# design.net
KiCad netlist of a schematic drawn in EasyEDA Pro
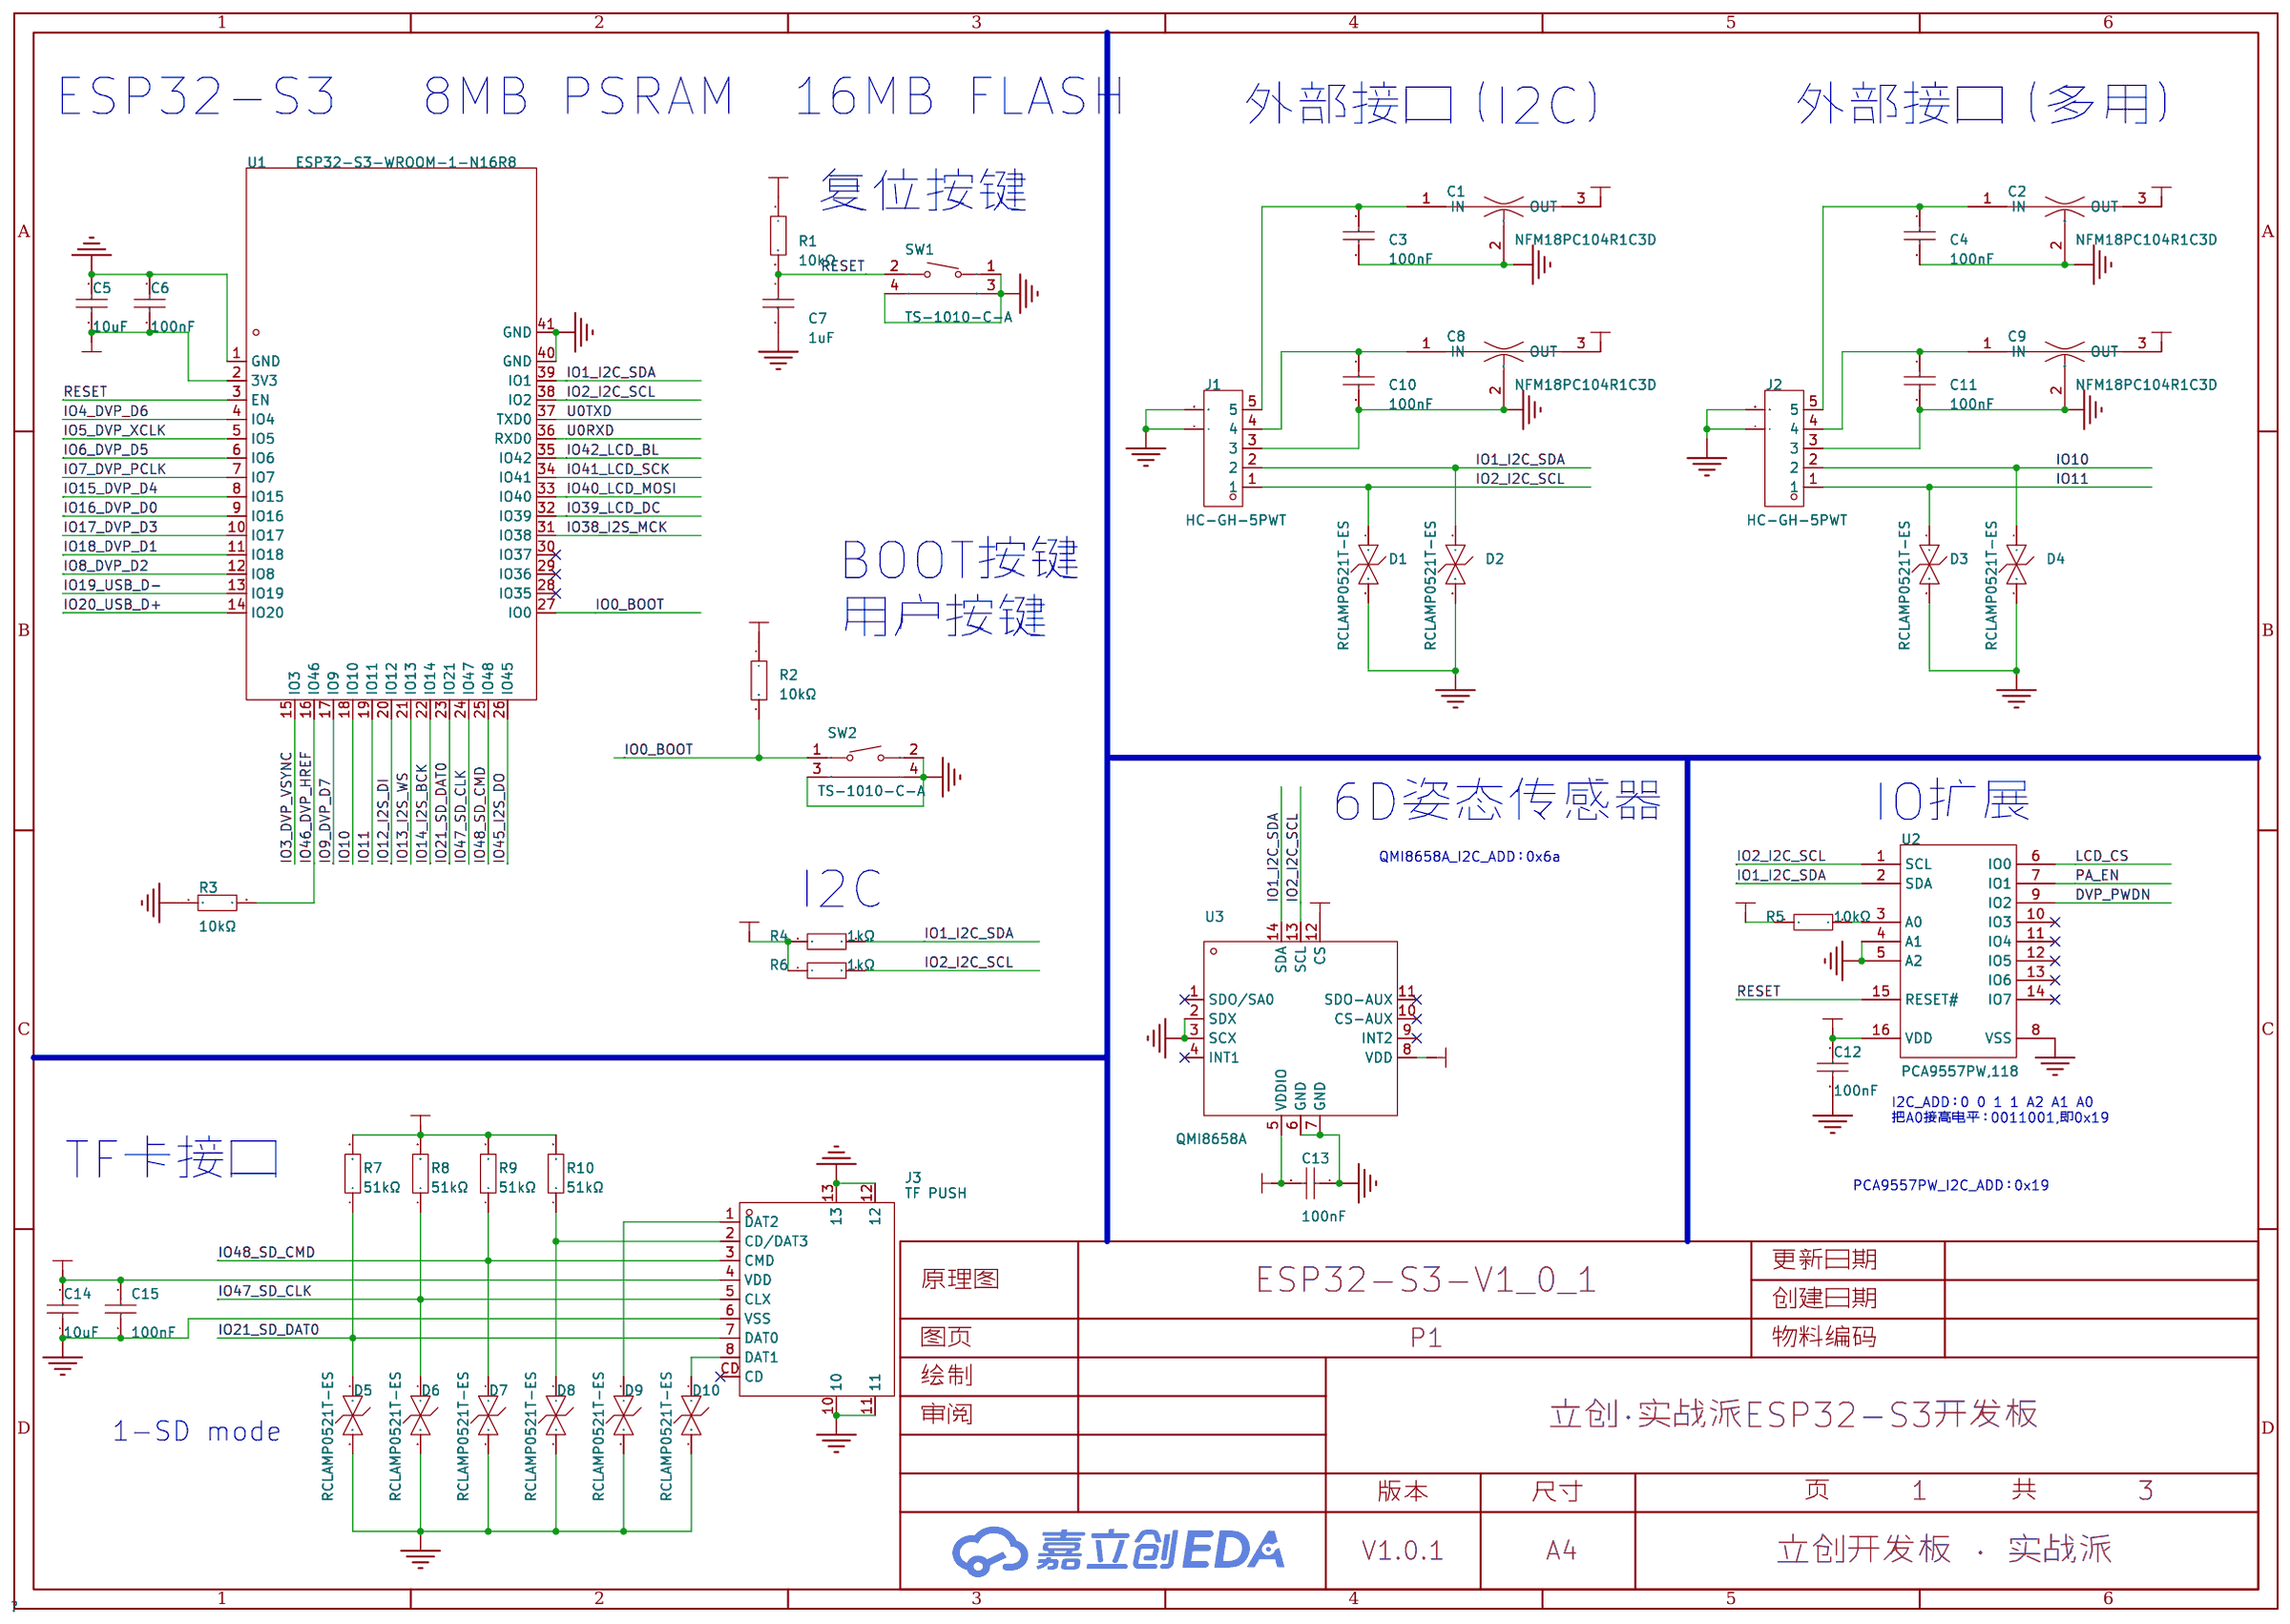
[diagram p0: P1]
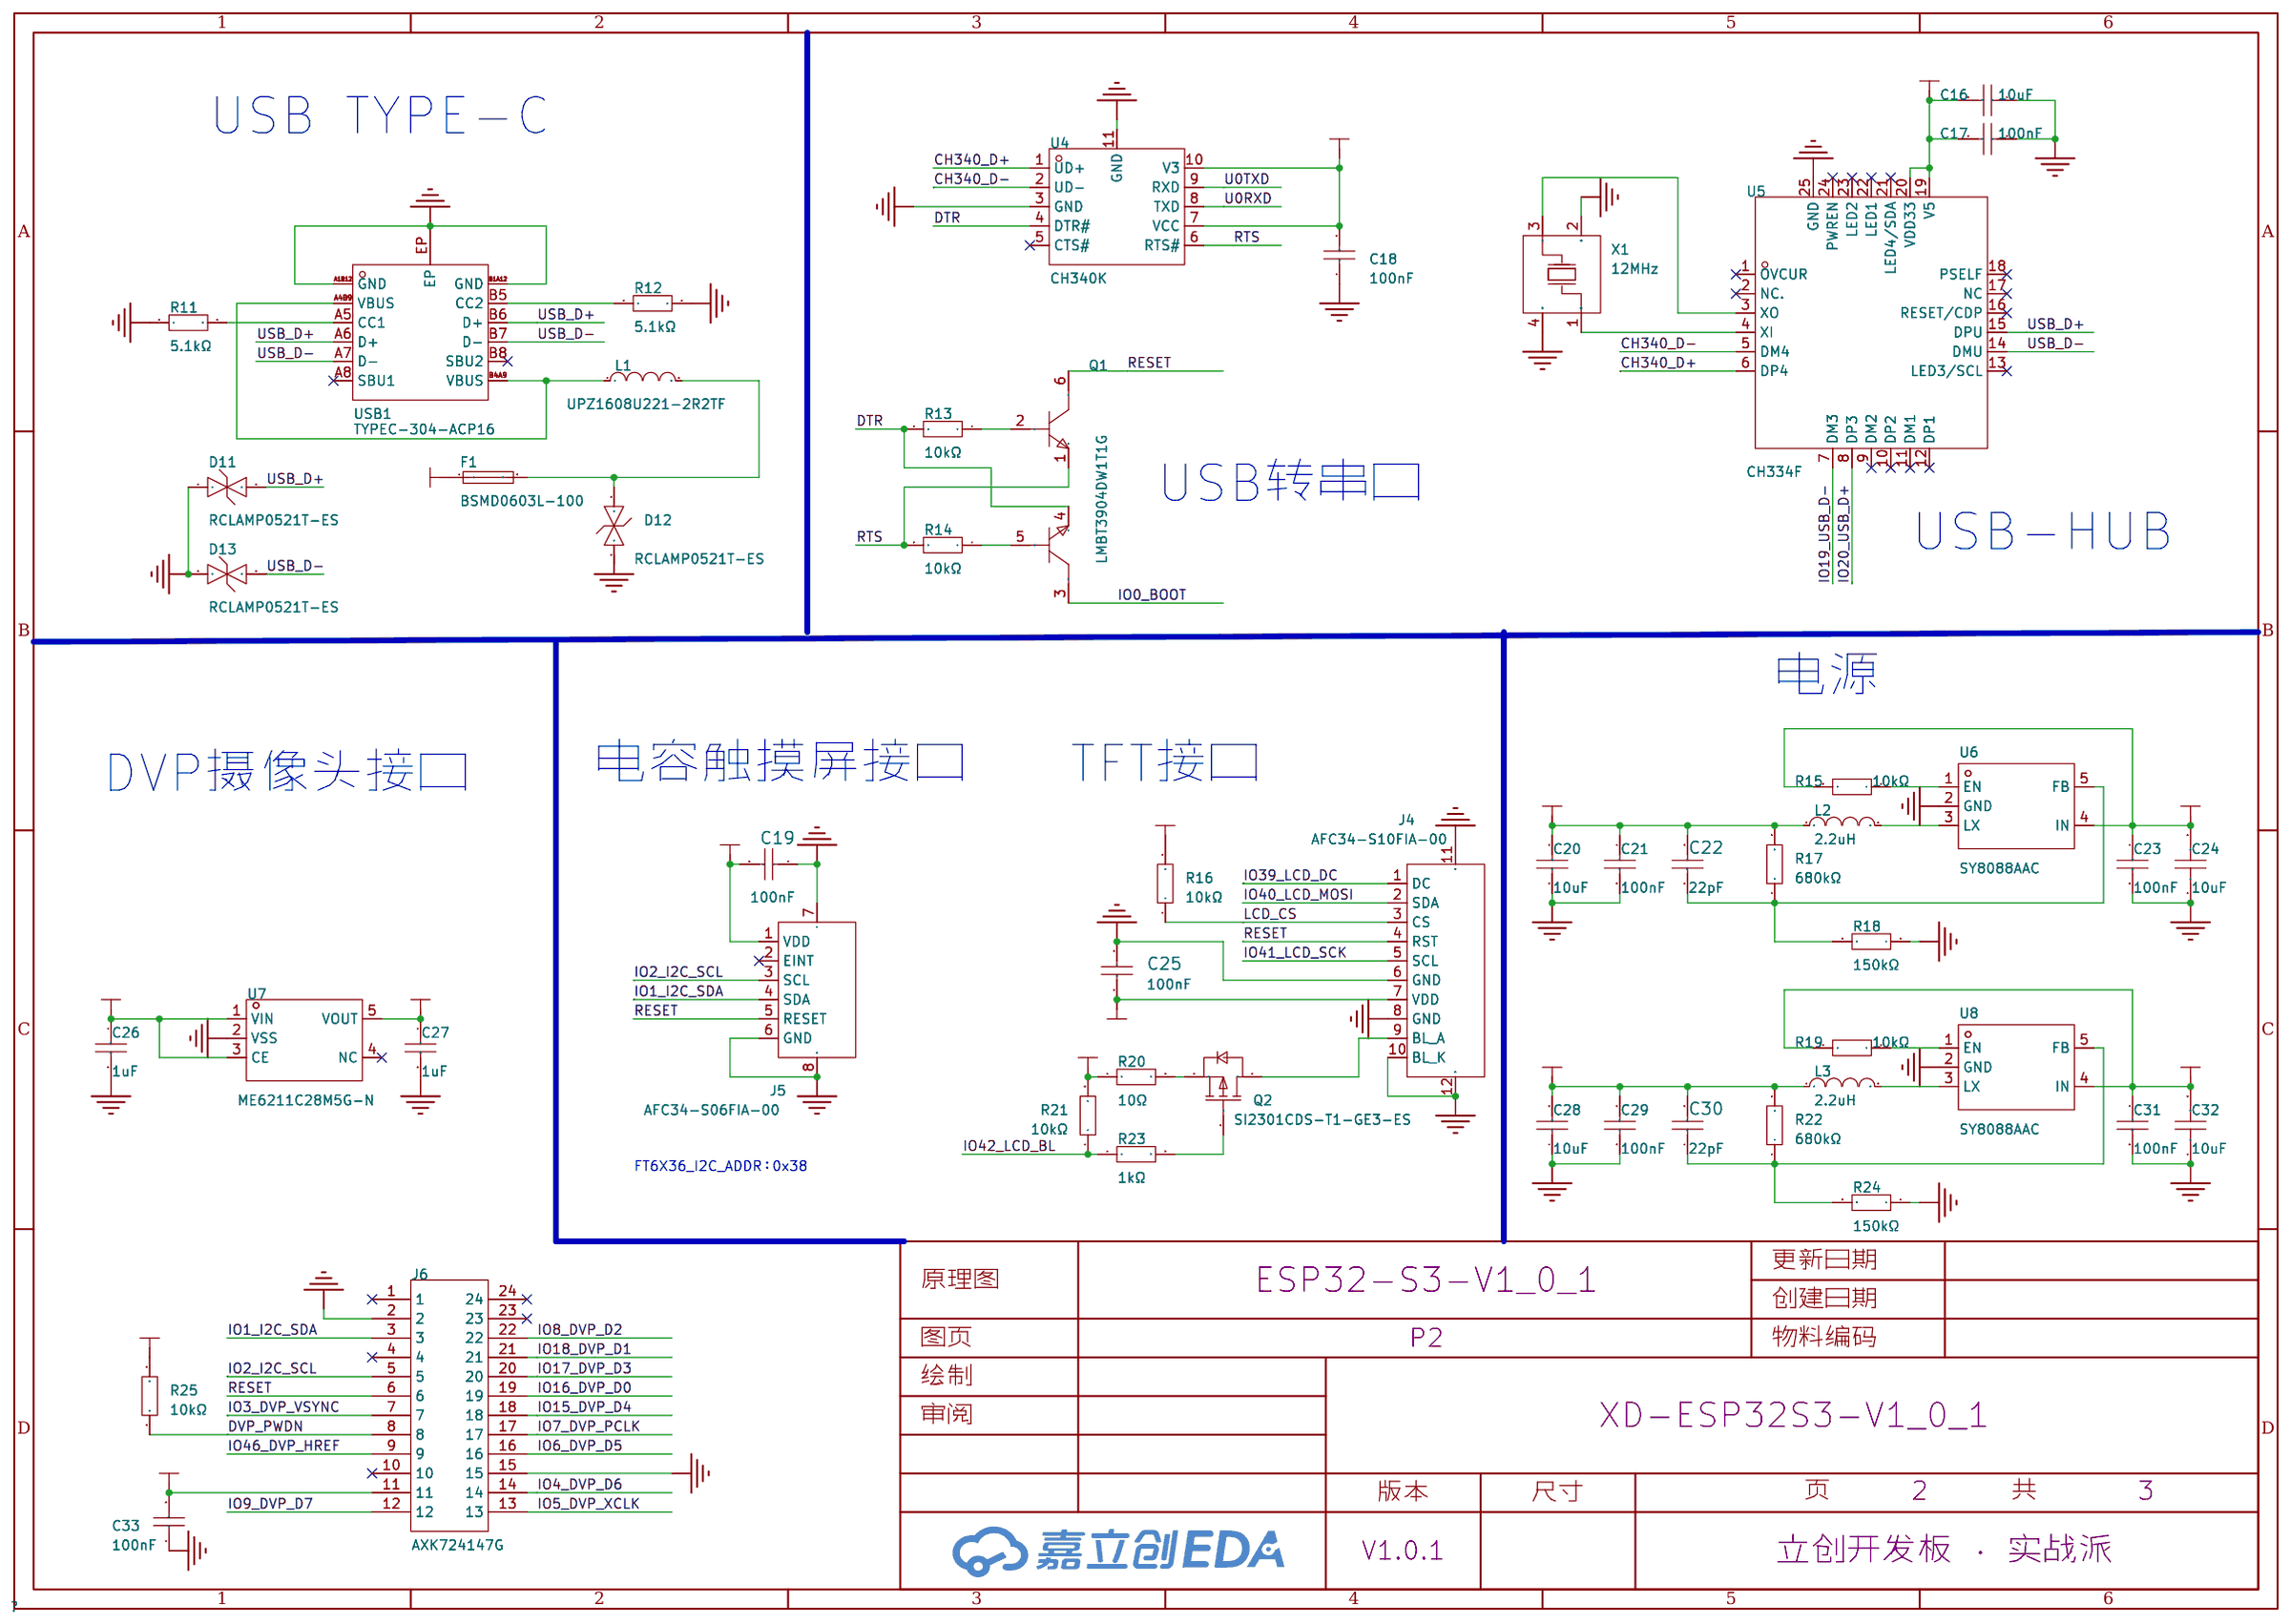
[diagram p1: P2]
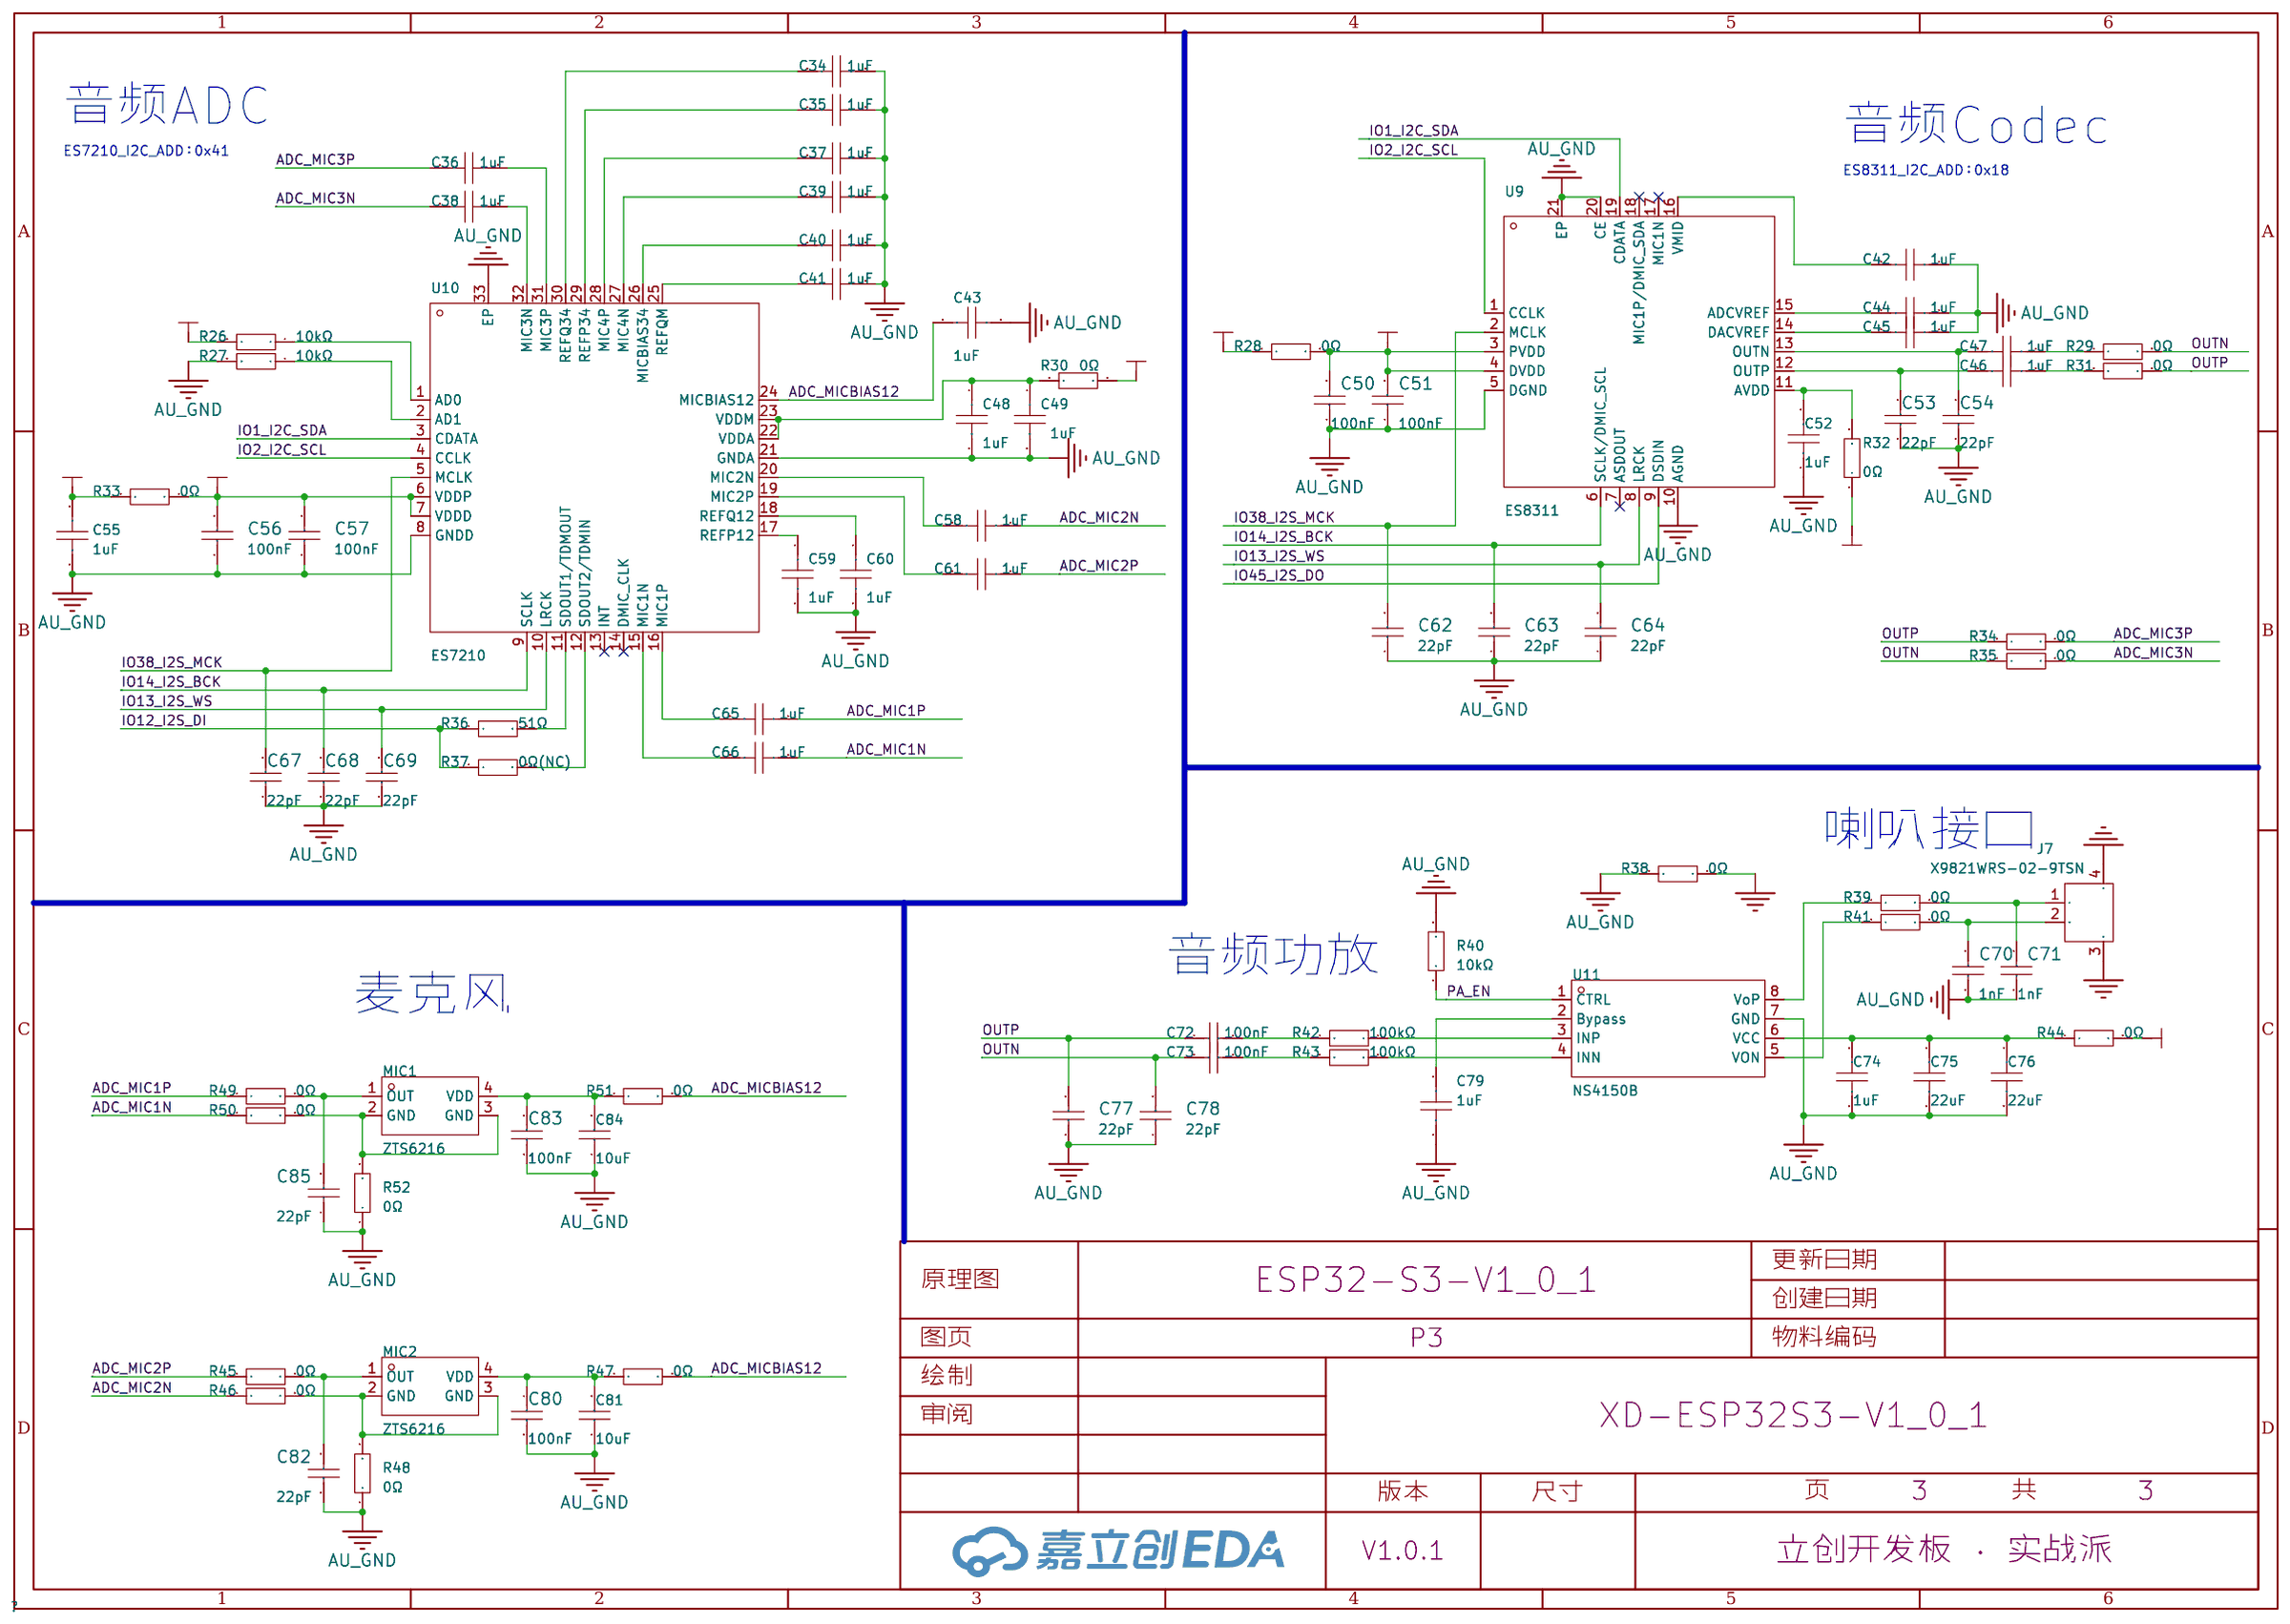
[diagram p2: P3]

(export (version "E")
  (design (tool "Eeschema 10.0.6"))
  (components
    (comp (ref "C1")
      (value "NFM18PC104R1C3D")
      (footprint "easyedapro:FILTER-SMD_3P-L1.6-W0.8-L_NFM18CC223R1C3D")
      (description "电容量:100nF;精度:±20%;直流电阻:30mΩ;")
      (fields (field (name "Manufacturer") "muRata(村田)"))
      (libsource (lib "easyedapro") (part "NFM15PC104D0J3D"))
    )
    (comp (ref "C2")
      (value "NFM18PC104R1C3D")
      (footprint "easyedapro:FILTER-SMD_3P-L1.6-W0.8-L_NFM18CC223R1C3D")
      (description "电容量:100nF;精度:±20%;直流电阻:30mΩ;")
      (fields (field (name "Manufacturer") "muRata(村田)"))
      (libsource (lib "easyedapro") (part "NFM15PC104D0J3D"))
    )
    (comp (ref "C3")
      (value "100nF")
      (footprint "easyedapro:C0402")
      (description "容值:100nF;精度:±10%;额定电压:16V;材质(温度系数):X7R;")
      (fields
        (field (name "Manufacturer Part") "CL05B104KO5NNNC")
        (field (name "Manufacturer") "SAMSUNG(三星)")
      )
      (libsource (lib "easyedapro") (part "CL05B104KO5NNNC"))
    )
    (comp (ref "C4")
      (value "100nF")
      (footprint "easyedapro:C0402")
      (description "容值:100nF;精度:±10%;额定电压:16V;材质(温度系数):X7R;")
      (fields
        (field (name "Manufacturer Part") "CL05B104KO5NNNC")
        (field (name "Manufacturer") "SAMSUNG(三星)")
      )
      (libsource (lib "easyedapro") (part "CL05B104KO5NNNC"))
    )
    (comp (ref "C5")
      (value "10uF")
      (footprint "easyedapro:C0402")
      (description "容值:10uF;精度:±20%;额定电压:6.3V;材质(温度系数):X5R;")
      (fields
        (field (name "Manufacturer Part") "CL05A106MQ5NUNC")
        (field (name "Manufacturer") "SAMSUNG(三星)")
      )
      (libsource (lib "easyedapro") (part "CL05A106MQ5NUNC"))
    )
    (comp (ref "C6")
      (value "100nF")
      (footprint "easyedapro:C0402")
      (description "容值:100nF;精度:±10%;额定电压:16V;材质(温度系数):X7R;")
      (fields
        (field (name "Manufacturer Part") "CL05B104KO5NNNC")
        (field (name "Manufacturer") "SAMSUNG(三星)")
      )
      (libsource (lib "easyedapro") (part "CL05B104KO5NNNC"))
    )
    (comp (ref "C7")
      (value "1uF")
      (footprint "easyedapro:C0402")
      (description "容值:100nF;精度:±10%;额定电压:16V;材质(温度系数):X7R;")
      (fields
        (field (name "Manufacturer Part") "CL05A105KA5NQNC")
        (field (name "Manufacturer") "SAMSUNG(三星)")
      )
      (libsource (lib "easyedapro") (part "CL05B104KO5NNNC"))
    )
    (comp (ref "C8")
      (value "NFM18PC104R1C3D")
      (footprint "easyedapro:FILTER-SMD_3P-L1.6-W0.8-L_NFM18CC223R1C3D")
      (description "电容量:100nF;精度:±20%;直流电阻:30mΩ;")
      (fields (field (name "Manufacturer") "muRata(村田)"))
      (libsource (lib "easyedapro") (part "NFM15PC104D0J3D"))
    )
    (comp (ref "C9")
      (value "NFM18PC104R1C3D")
      (footprint "easyedapro:FILTER-SMD_3P-L1.6-W0.8-L_NFM18CC223R1C3D")
      (description "电容量:100nF;精度:±20%;直流电阻:30mΩ;")
      (fields (field (name "Manufacturer") "muRata(村田)"))
      (libsource (lib "easyedapro") (part "NFM15PC104D0J3D"))
    )
    (comp (ref "C10")
      (value "100nF")
      (footprint "easyedapro:C0402")
      (description "容值:100nF;精度:±10%;额定电压:16V;材质(温度系数):X7R;")
      (fields
        (field (name "Manufacturer Part") "CL05B104KO5NNNC")
        (field (name "Manufacturer") "SAMSUNG(三星)")
      )
      (libsource (lib "easyedapro") (part "CL05B104KO5NNNC"))
    )
    (comp (ref "C11")
      (value "100nF")
      (footprint "easyedapro:C0402")
      (description "容值:100nF;精度:±10%;额定电压:16V;材质(温度系数):X7R;")
      (fields
        (field (name "Manufacturer Part") "CL05B104KO5NNNC")
        (field (name "Manufacturer") "SAMSUNG(三星)")
      )
      (libsource (lib "easyedapro") (part "CL05B104KO5NNNC"))
    )
    (comp (ref "C12")
      (value "100nF")
      (footprint "easyedapro:C0402")
      (description "容值:100nF;精度:±10%;额定电压:16V;材质(温度系数):X7R;")
      (fields
        (field (name "Manufacturer Part") "CL05B104KO5NNNC")
        (field (name "Manufacturer") "SAMSUNG(三星)")
      )
      (libsource (lib "easyedapro") (part "CL05B104KO5NNNC"))
    )
    (comp (ref "C13")
      (value "100nF")
      (footprint "easyedapro:C0402")
      (description "容值:100nF;精度:±10%;额定电压:16V;材质(温度系数):X7R;")
      (fields
        (field (name "Manufacturer Part") "CL05B104KO5NNNC")
        (field (name "Manufacturer") "SAMSUNG(三星)")
      )
      (libsource (lib "easyedapro") (part "CL05B104KO5NNNC"))
    )
    (comp (ref "C14")
      (value "10uF")
      (footprint "easyedapro:C0402")
      (description "容值:10uF;精度:±20%;额定电压:6.3V;材质(温度系数):X5R;")
      (fields
        (field (name "Manufacturer Part") "CL05A106MQ5NUNC")
        (field (name "Manufacturer") "SAMSUNG(三星)")
      )
      (libsource (lib "easyedapro") (part "CL05A106MQ5NUNC"))
    )
    (comp (ref "C15")
      (value "100nF")
      (footprint "easyedapro:C0402")
      (description "容值:100nF;精度:±10%;额定电压:16V;材质(温度系数):X7R;")
      (fields
        (field (name "Manufacturer Part") "CL05B104KO5NNNC")
        (field (name "Manufacturer") "SAMSUNG(三星)")
      )
      (libsource (lib "easyedapro") (part "CL05B104KO5NNNC"))
    )
    (comp (ref "D1")
      (value "RCLAMP0521T-ES")
      (footprint "easyedapro:DFN1006-2L-BI")
      (description "反向关断电压（典型值）:5V(Max) 击穿电压（最小值）:6.0V 箝位电压:12V 峰值脉冲电流:4A (8/20us) 极性:Bidirectional")
      (fields (field (name "Manufacturer") "ElecSuper(静芯微）"))
      (libsource (lib "easyedapro") (part "RCLAMP0521T-ES"))
    )
    (comp (ref "D2")
      (value "RCLAMP0521T-ES")
      (footprint "easyedapro:DFN1006-2L-BI")
      (description "反向关断电压（典型值）:5V(Max) 击穿电压（最小值）:6.0V 箝位电压:12V 峰值脉冲电流:4A (8/20us) 极性:Bidirectional")
      (fields (field (name "Manufacturer") "ElecSuper(静芯微）"))
      (libsource (lib "easyedapro") (part "RCLAMP0521T-ES"))
    )
    (comp (ref "D3")
      (value "RCLAMP0521T-ES")
      (footprint "easyedapro:DFN1006-2L-BI")
      (description "反向关断电压（典型值）:5V(Max) 击穿电压（最小值）:6.0V 箝位电压:12V 峰值脉冲电流:4A (8/20us) 极性:Bidirectional")
      (fields (field (name "Manufacturer") "ElecSuper(静芯微）"))
      (libsource (lib "easyedapro") (part "RCLAMP0521T-ES"))
    )
    (comp (ref "D4")
      (value "RCLAMP0521T-ES")
      (footprint "easyedapro:DFN1006-2L-BI")
      (description "反向关断电压（典型值）:5V(Max) 击穿电压（最小值）:6.0V 箝位电压:12V 峰值脉冲电流:4A (8/20us) 极性:Bidirectional")
      (fields (field (name "Manufacturer") "ElecSuper(静芯微）"))
      (libsource (lib "easyedapro") (part "RCLAMP0521T-ES"))
    )
    (comp (ref "D5")
      (value "RCLAMP0521T-ES")
      (footprint "easyedapro:DFN1006-2L-BI")
      (description "反向关断电压（典型值）:5V(Max) 击穿电压（最小值）:6.0V 箝位电压:12V 峰值脉冲电流:4A (8/20us) 极性:Bidirectional")
      (fields (field (name "Manufacturer") "ElecSuper(静芯微）"))
      (libsource (lib "easyedapro") (part "RCLAMP0521T-ES"))
    )
    (comp (ref "D6")
      (value "RCLAMP0521T-ES")
      (footprint "easyedapro:DFN1006-2L-BI")
      (description "反向关断电压（典型值）:5V(Max) 击穿电压（最小值）:6.0V 箝位电压:12V 峰值脉冲电流:4A (8/20us) 极性:Bidirectional")
      (fields (field (name "Manufacturer") "ElecSuper(静芯微）"))
      (libsource (lib "easyedapro") (part "RCLAMP0521T-ES"))
    )
    (comp (ref "D7")
      (value "RCLAMP0521T-ES")
      (footprint "easyedapro:DFN1006-2L-BI")
      (description "反向关断电压（典型值）:5V(Max) 击穿电压（最小值）:6.0V 箝位电压:12V 峰值脉冲电流:4A (8/20us) 极性:Bidirectional")
      (fields (field (name "Manufacturer") "ElecSuper(静芯微）"))
      (libsource (lib "easyedapro") (part "RCLAMP0521T-ES"))
    )
    (comp (ref "D8")
      (value "RCLAMP0521T-ES")
      (footprint "easyedapro:DFN1006-2L-BI")
      (description "反向关断电压（典型值）:5V(Max) 击穿电压（最小值）:6.0V 箝位电压:12V 峰值脉冲电流:4A (8/20us) 极性:Bidirectional")
      (fields (field (name "Manufacturer") "ElecSuper(静芯微）"))
      (libsource (lib "easyedapro") (part "RCLAMP0521T-ES"))
    )
    (comp (ref "D9")
      (value "RCLAMP0521T-ES")
      (footprint "easyedapro:DFN1006-2L-BI")
      (description "反向关断电压（典型值）:5V(Max) 击穿电压（最小值）:6.0V 箝位电压:12V 峰值脉冲电流:4A (8/20us) 极性:Bidirectional")
      (fields (field (name "Manufacturer") "ElecSuper(静芯微）"))
      (libsource (lib "easyedapro") (part "RCLAMP0521T-ES"))
    )
    (comp (ref "D10")
      (value "RCLAMP0521T-ES")
      (footprint "easyedapro:DFN1006-2L-BI")
      (description "反向关断电压（典型值）:5V(Max) 击穿电压（最小值）:6.0V 箝位电压:12V 峰值脉冲电流:4A (8/20us) 极性:Bidirectional")
      (fields (field (name "Manufacturer") "ElecSuper(静芯微）"))
      (libsource (lib "easyedapro") (part "RCLAMP0521T-ES"))
    )
    (comp (ref "J1")
      (value "HC-GH-5PWT")
      (footprint "easyedapro:CONN-SMD_5P-P1.25_HC-GH-5PWTKK")
      (description "插针结构:1x5P;间距:1.25mm;公母:公;安装方式:卧贴;排数:1;每排PIN数:5;参考系列:GH;额定电流:1A;工作温度范围:-25°C~+85°C;")
      (fields (field (name "Manufacturer") "HCTL(华灿天禄)"))
      (libsource (lib "easyedapro") (part "HC-GH-5PWT_C3011947"))
    )
    (comp (ref "J2")
      (value "HC-GH-5PWT")
      (footprint "easyedapro:CONN-SMD_5P-P1.25_HC-GH-5PWTKK")
      (description "插针结构:1x5P;间距:1.25mm;公母:公;安装方式:卧贴;排数:1;每排PIN数:5;参考系列:GH;额定电流:1A;工作温度范围:-25°C~+85°C;")
      (fields (field (name "Manufacturer") "HCTL(华灿天禄)"))
      (libsource (lib "easyedapro") (part "HC-GH-5PWT_C3011947"))
    )
    (comp (ref "J3")
      (value "TF PUSH")
      (footprint "easyedapro:TF-SMD_TF-PUSH")
      (description "卡连接方式:自弹式;卡类型:MicroSD卡(TF卡);连接器类型:卡座;本体最大高度:2mm;触头材质:-;触头镀层:-;工作温度范围:-20°C~+90°C;焊接温度(最大值):-;")
      (fields (field (name "Manufacturer") "SHOU HAN(首韩)"))
      (libsource (lib "easyedapro") (part "TF PUSH"))
    )
    (comp (ref "R1")
      (value "10kΩ")
      (footprint "easyedapro:R0402")
      (description "电阻类型:厚膜电阻;阻值:10kΩ;精度:±1%;功率:62.5mW;温度系数:±100ppm/°C;")
      (fields
        (field (name "Manufacturer Part") "0402WGF1002TCE")
        (field (name "Manufacturer") "UNI-ROYAL(厚声)")
      )
      (libsource (lib "easyedapro") (part "0402WGF1002TCE"))
    )
    (comp (ref "R2")
      (value "10kΩ")
      (footprint "easyedapro:R0402")
      (description "电阻类型:厚膜电阻;阻值:10kΩ;精度:±1%;功率:62.5mW;温度系数:±100ppm/°C;")
      (fields
        (field (name "Manufacturer Part") "0402WGF1002TCE")
        (field (name "Manufacturer") "UNI-ROYAL(厚声)")
      )
      (libsource (lib "easyedapro") (part "0402WGF1002TCE"))
    )
    (comp (ref "R3")
      (value "10kΩ")
      (footprint "easyedapro:R0402")
      (description "电阻类型:厚膜电阻;阻值:10kΩ;精度:±1%;功率:62.5mW;温度系数:±100ppm/°C;")
      (fields
        (field (name "Manufacturer Part") "0402WGF1002TCE")
        (field (name "Manufacturer") "UNI-ROYAL(厚声)")
      )
      (libsource (lib "easyedapro") (part "0402WGF1002TCE"))
    )
    (comp (ref "R4")
      (value "1kΩ")
      (footprint "easyedapro:R0402")
      (description "电阻类型:厚膜电阻;阻值:1kΩ;精度:±1%;功率:62.5mW;")
      (fields
        (field (name "Manufacturer Part") "0402WGF1001TCE")
        (field (name "Manufacturer") "UNI-ROYAL(厚声)")
      )
      (libsource (lib "easyedapro") (part "0402WGF1001TCE"))
    )
    (comp (ref "R5")
      (value "10kΩ")
      (footprint "easyedapro:R0402")
      (description "电阻类型:厚膜电阻;阻值:10kΩ;精度:±1%;功率:62.5mW;温度系数:±100ppm/°C;")
      (fields
        (field (name "Manufacturer Part") "0402WGF1002TCE")
        (field (name "Manufacturer") "UNI-ROYAL(厚声)")
      )
      (libsource (lib "easyedapro") (part "0402WGF1002TCE"))
    )
    (comp (ref "R6")
      (value "1kΩ")
      (footprint "easyedapro:R0402")
      (description "电阻类型:厚膜电阻;阻值:1kΩ;精度:±1%;功率:62.5mW;")
      (fields
        (field (name "Manufacturer Part") "0402WGF1001TCE")
        (field (name "Manufacturer") "UNI-ROYAL(厚声)")
      )
      (libsource (lib "easyedapro") (part "0402WGF1001TCE"))
    )
    (comp (ref "R7")
      (value "51kΩ")
      (footprint "easyedapro:R0402")
      (description "电阻类型:厚膜电阻;阻值:51kΩ;精度:±1%;功率:62.5mW;最大工作电压:50V;温度系数:±100ppm/°C;")
      (fields
        (field (name "Manufacturer Part") "0402WGF5102TCE")
        (field (name "Manufacturer") "UNI-ROYAL(厚声)")
      )
      (libsource (lib "easyedapro") (part "0402WGF5102TCE"))
    )
    (comp (ref "R8")
      (value "51kΩ")
      (footprint "easyedapro:R0402")
      (description "电阻类型:厚膜电阻;阻值:51kΩ;精度:±1%;功率:62.5mW;最大工作电压:50V;温度系数:±100ppm/°C;")
      (fields
        (field (name "Manufacturer Part") "0402WGF5102TCE")
        (field (name "Manufacturer") "UNI-ROYAL(厚声)")
      )
      (libsource (lib "easyedapro") (part "0402WGF5102TCE"))
    )
    (comp (ref "R9")
      (value "51kΩ")
      (footprint "easyedapro:R0402")
      (description "电阻类型:厚膜电阻;阻值:51kΩ;精度:±1%;功率:62.5mW;最大工作电压:50V;温度系数:±100ppm/°C;")
      (fields
        (field (name "Manufacturer Part") "0402WGF5102TCE")
        (field (name "Manufacturer") "UNI-ROYAL(厚声)")
      )
      (libsource (lib "easyedapro") (part "0402WGF5102TCE"))
    )
    (comp (ref "R10")
      (value "51kΩ")
      (footprint "easyedapro:R0402")
      (description "电阻类型:厚膜电阻;阻值:51kΩ;精度:±1%;功率:62.5mW;最大工作电压:50V;温度系数:±100ppm/°C;")
      (fields
        (field (name "Manufacturer Part") "0402WGF5102TCE")
        (field (name "Manufacturer") "UNI-ROYAL(厚声)")
      )
      (libsource (lib "easyedapro") (part "0402WGF5102TCE"))
    )
    (comp (ref "SW1")
      (value "TS-1010-C-A")
      (footprint "easyedapro:KEY-SMD_TX-1010-X-X")
      (fields (field (name "Manufacturer") "XKB Connectivity(中国星坤)"))
      (libsource (lib "easyedapro") (part "TS-1010-C-A"))
    )
    (comp (ref "SW2")
      (value "TS-1010-C-A")
      (footprint "easyedapro:KEY-SMD_TX-1010-X-X")
      (fields (field (name "Manufacturer") "XKB Connectivity(中国星坤)"))
      (libsource (lib "easyedapro") (part "TS-1010-C-A"))
    )
    (comp (ref "U1")
      (value "ESP32-S3-WROOM-1-N16R8")
      (footprint "easyedapro:WIRELM-SMD_ESP32-S3-WROOM-1")
      (fields (field (name "Manufacturer") "ESPRESSIF(乐鑫)"))
      (libsource (lib "easyedapro") (part "ESP32-S3-WROOM-1(N16R8)"))
    )
    (comp (ref "U2")
      (value "PCA9557PW,118")
      (footprint "easyedapro:TSSOP-16_L5.0-W4.4-P0.65-LS6.4-BL")
      (description "接口:I2C；SMBus;I/O数量:8;时钟频率:400kHz;")
      (fields (field (name "Manufacturer") "NXP(恩智浦)"))
      (libsource (lib "easyedapro") (part "PCA9557PW,118"))
    )
    (comp (ref "U3")
      (value "QMI8658A")
      (footprint "easyedapro:LGA-14_L3.0-W2.5-P0.50-TL")
      (fields (field (name "Manufacturer") "QST(上海矽睿)"))
      (libsource (lib "easyedapro") (part "QMI8658A_C3021082"))
    )
    (comp (ref "C16")
      (value "10uF")
      (footprint "easyedapro:C0402")
      (description "容值:10uF;精度:±20%;额定电压:6.3V;材质(温度系数):X5R;")
      (fields
        (field (name "Manufacturer Part") "CL05A106MQ5NUNC")
        (field (name "Manufacturer") "SAMSUNG(三星)")
      )
      (libsource (lib "easyedapro") (part "CL05A106MQ5NUNC"))
    )
    (comp (ref "C17")
      (value "100nF")
      (footprint "easyedapro:C0402")
      (description "容值:100nF;精度:±10%;额定电压:16V;材质(温度系数):X7R;")
      (fields
        (field (name "Manufacturer Part") "CL05B104KO5NNNC")
        (field (name "Manufacturer") "SAMSUNG(三星)")
      )
      (libsource (lib "easyedapro") (part "CL05B104KO5NNNC"))
    )
    (comp (ref "C18")
      (value "100nF")
      (footprint "easyedapro:C0402")
      (description "容值:100nF;精度:±10%;额定电压:16V;材质(温度系数):X7R;")
      (fields
        (field (name "Manufacturer Part") "CL05B104KO5NNNC")
        (field (name "Manufacturer") "SAMSUNG(三星)")
      )
      (libsource (lib "easyedapro") (part "CL05B104KO5NNNC"))
    )
    (comp (ref "C19")
      (value "100nF")
      (footprint "easyedapro:C0402")
      (description "温度系数:X7R;容值:100nF;精度:±10%;额定电压:50V;")
      (fields (field (name "Manufacturer Part") "0402B104K500NT") (field (name "Manufacturer") "FH(风华)"))
      (libsource (lib "easyedapro") (part "0402B104K500NT"))
    )
    (comp (ref "C20")
      (value "10uF")
      (footprint "easyedapro:C0402")
      (description "容值:10uF;精度:±20%;额定电压:6.3V;材质(温度系数):X5R;")
      (fields
        (field (name "Manufacturer Part") "CL05A106MQ5NUNC")
        (field (name "Manufacturer") "SAMSUNG(三星)")
      )
      (libsource (lib "easyedapro") (part "CL05A106MQ5NUNC"))
    )
    (comp (ref "C21")
      (value "100nF")
      (footprint "easyedapro:C0402")
      (description "容值:100nF;精度:±10%;额定电压:16V;材质(温度系数):X7R;")
      (fields
        (field (name "Manufacturer Part") "CL05B104KO5NNNC")
        (field (name "Manufacturer") "SAMSUNG(三星)")
      )
      (libsource (lib "easyedapro") (part "CL05B104KO5NNNC"))
    )
    (comp (ref "C22")
      (value "22pF")
      (footprint "easyedapro:C0402")
      (description "容值:22pF;精度:±5%;额定电压:50V;材质(温度系数):C0G;")
      (fields (field (name "Manufacturer Part") "0402CG220J500NT") (field (name "Manufacturer") "FH(风华)"))
      (libsource (lib "easyedapro") (part "0402CG220J500NT"))
    )
    (comp (ref "C23")
      (value "100nF")
      (footprint "easyedapro:C0402")
      (description "容值:100nF;精度:±10%;额定电压:16V;材质(温度系数):X7R;")
      (fields
        (field (name "Manufacturer Part") "CL05B104KO5NNNC")
        (field (name "Manufacturer") "SAMSUNG(三星)")
      )
      (libsource (lib "easyedapro") (part "CL05B104KO5NNNC"))
    )
    (comp (ref "C24")
      (value "10uF")
      (footprint "easyedapro:C0603")
      (description "容值:10uF;精度:±20%;额定电压:25V;材质(温度系数):X5R;")
      (fields
        (field (name "Manufacturer Part") "CL10A106MA8NRNC")
        (field (name "Manufacturer") "SAMSUNG(三星)")
      )
      (libsource (lib "easyedapro") (part "CL10A106MA8NRNC"))
    )
    (comp (ref "C25")
      (value "100nF")
      (footprint "easyedapro:C0402")
      (description "温度系数:X7R;容值:100nF;精度:±10%;额定电压:50V;")
      (fields (field (name "Manufacturer Part") "0402B104K500NT") (field (name "Manufacturer") "FH(风华)"))
      (libsource (lib "easyedapro") (part "0402B104K500NT"))
    )
    (comp (ref "C26")
      (value "1uF")
      (footprint "easyedapro:C0402")
      (description "容值:100nF;精度:±10%;额定电压:16V;材质(温度系数):X7R;")
      (fields
        (field (name "Manufacturer Part") "CL05A105KA5NQNC")
        (field (name "Manufacturer") "SAMSUNG(三星)")
      )
      (libsource (lib "easyedapro") (part "CL05B104KO5NNNC"))
    )
    (comp (ref "C27")
      (value "1uF")
      (footprint "easyedapro:C0402")
      (description "容值:100nF;精度:±10%;额定电压:16V;材质(温度系数):X7R;")
      (fields
        (field (name "Manufacturer Part") "CL05A105KA5NQNC")
        (field (name "Manufacturer") "SAMSUNG(三星)")
      )
      (libsource (lib "easyedapro") (part "CL05B104KO5NNNC"))
    )
    (comp (ref "C28")
      (value "10uF")
      (footprint "easyedapro:C0402")
      (description "容值:10uF;精度:±20%;额定电压:6.3V;材质(温度系数):X5R;")
      (fields
        (field (name "Manufacturer Part") "CL05A106MQ5NUNC")
        (field (name "Manufacturer") "SAMSUNG(三星)")
      )
      (libsource (lib "easyedapro") (part "CL05A106MQ5NUNC"))
    )
    (comp (ref "C29")
      (value "100nF")
      (footprint "easyedapro:C0402")
      (description "容值:100nF;精度:±10%;额定电压:16V;材质(温度系数):X7R;")
      (fields
        (field (name "Manufacturer Part") "CL05B104KO5NNNC")
        (field (name "Manufacturer") "SAMSUNG(三星)")
      )
      (libsource (lib "easyedapro") (part "CL05B104KO5NNNC"))
    )
    (comp (ref "C30")
      (value "22pF")
      (footprint "easyedapro:C0402")
      (description "容值:22pF;精度:±5%;额定电压:50V;材质(温度系数):C0G;")
      (fields (field (name "Manufacturer Part") "0402CG220J500NT") (field (name "Manufacturer") "FH(风华)"))
      (libsource (lib "easyedapro") (part "0402CG220J500NT"))
    )
    (comp (ref "C31")
      (value "100nF")
      (footprint "easyedapro:C0402")
      (description "容值:100nF;精度:±10%;额定电压:16V;材质(温度系数):X7R;")
      (fields
        (field (name "Manufacturer Part") "CL05B104KO5NNNC")
        (field (name "Manufacturer") "SAMSUNG(三星)")
      )
      (libsource (lib "easyedapro") (part "CL05B104KO5NNNC"))
    )
    (comp (ref "C32")
      (value "10uF")
      (footprint "easyedapro:C0603")
      (description "容值:10uF;精度:±20%;额定电压:25V;材质(温度系数):X5R;")
      (fields
        (field (name "Manufacturer Part") "CL10A106MA8NRNC")
        (field (name "Manufacturer") "SAMSUNG(三星)")
      )
      (libsource (lib "easyedapro") (part "CL10A106MA8NRNC"))
    )
    (comp (ref "C33")
      (value "100nF")
      (footprint "easyedapro:C0402")
      (description "容值:100nF;精度:±10%;额定电压:16V;材质(温度系数):X7R;")
      (fields
        (field (name "Manufacturer Part") "CL05B104KO5NNNC")
        (field (name "Manufacturer") "SAMSUNG(三星)")
      )
      (libsource (lib "easyedapro") (part "CL05B104KO5NNNC"))
    )
    (comp (ref "D11")
      (value "RCLAMP0521T-ES")
      (footprint "easyedapro:DFN1006-2L-BI")
      (description "反向关断电压（典型值）:5V(Max) 击穿电压（最小值）:6.0V 箝位电压:12V 峰值脉冲电流:4A (8/20us) 极性:Bidirectional")
      (fields (field (name "Manufacturer") "ElecSuper(静芯微）"))
      (libsource (lib "easyedapro") (part "RCLAMP0521T-ES"))
    )
    (comp (ref "D12")
      (value "RCLAMP0521T-ES")
      (footprint "easyedapro:DFN1006-2L-BI")
      (description "反向关断电压（典型值）:5V(Max) 击穿电压（最小值）:6.0V 箝位电压:12V 峰值脉冲电流:4A (8/20us) 极性:Bidirectional")
      (fields (field (name "Manufacturer") "ElecSuper(静芯微）"))
      (libsource (lib "easyedapro") (part "RCLAMP0521T-ES"))
    )
    (comp (ref "D13")
      (value "RCLAMP0521T-ES")
      (footprint "easyedapro:DFN1006-2L-BI")
      (description "反向关断电压（典型值）:5V(Max) 击穿电压（最小值）:6.0V 箝位电压:12V 峰值脉冲电流:4A (8/20us) 极性:Bidirectional")
      (fields (field (name "Manufacturer") "ElecSuper(静芯微）"))
      (libsource (lib "easyedapro") (part "RCLAMP0521T-ES"))
    )
    (comp (ref "F1")
      (value "BSMD0603L-100")
      (footprint "easyedapro:F0603")
      (description "最大电压:6V;最大电流:50A;保持电流:1A;跳闸电流:2A;")
      (fields (field (name "Manufacturer") "BHFUSE(佰宏)"))
      (libsource (lib "easyedapro") (part "BSMD0603L-100"))
    )
    (comp (ref "J4")
      (value "AFC34-S10FIA-00")
      (footprint "easyedapro:FPC-SMD_AFC34-S10FIA-00")
      (description "间距:0.5mm;触点数量:10P;锁定特性:翻盖式;安装类型:卧贴;触点类型:双侧触点/上下接;工作温度范围:-;")
      (fields (field (name "Manufacturer") "JS(钜硕电子)"))
      (libsource (lib "easyedapro") (part "SPI_TFT_ST7789_10P"))
    )
    (comp (ref "J5")
      (value "AFC34-S06FIA-00")
      (footprint "easyedapro:FPC-SMD_AFC34-S06FIA-00")
      (description "间距:0.5mm;触点数量:6P;锁定特性:翻盖式;安装类型:卧贴;触点类型:双侧触点/上下接;工作温度范围:-;")
      (fields (field (name "Manufacturer") "JS(钜硕电子)"))
      (libsource (lib "easyedapro") (part "LCD_TOUCH_FT6X36"))
    )
    (comp (ref "J6")
      (value "AXK724147G")
      (footprint "easyedapro:CONN-SMD_AXK724147G")
      (description "PIN总数:24P;间距:0.4mm;公母:母;安装方式:立贴;行数:2;")
      (fields (field (name "Manufacturer") "PANASONIC(松下)"))
      (libsource (lib "easyedapro") (part "AXK724147G"))
    )
    (comp (ref "L1")
      (value "UPZ1608U221-2R2TF")
      (footprint "easyedapro:L0603")
      (description "标称阻抗@测试频率:220Ω@100MHz;误差:±25%;直流电阻(RDC):50mΩ;额定电流:2.2A;电路数:1;")
      (fields (field (name "Manufacturer") "Sunlord(顺络)"))
      (libsource (lib "easyedapro") (part "UPZ1608U221-2R2TF"))
    )
    (comp (ref "L2")
      (value "2.2uH")
      (footprint "easyedapro:IND-SMD_L2.5-W2.0-VLS252012CX-150M")
      (description "电感值:2.2uH;精度:±20%;额定电流:3A;饱和电流(Isat):3.3A;类型:一体成型电感;")
      (fields
        (field (name "Manufacturer Part") "FXLB252012-2R2-M")
        (field (name "Manufacturer") "cjiang(长江微电)")
      )
      (libsource (lib "easyedapro") (part "FXLB252012-2R2-M"))
    )
    (comp (ref "L3")
      (value "2.2uH")
      (footprint "easyedapro:IND-SMD_L2.5-W2.0-VLS252012CX-150M")
      (description "电感值:2.2uH;精度:±20%;额定电流:3A;饱和电流(Isat):3.3A;类型:一体成型电感;")
      (fields
        (field (name "Manufacturer Part") "FXLB252012-2R2-M")
        (field (name "Manufacturer") "cjiang(长江微电)")
      )
      (libsource (lib "easyedapro") (part "FXLB252012-2R2-M"))
    )
    (comp (ref "Q1")
      (value "LMBT3904DW1T1G")
      (footprint "easyedapro:SOT-363_L2.0-W1.3-P0.65-LS2.1-BR")
      (description "晶体管类型:2个NPN;集射极击穿电压(Vceo):40V;集电极电流(Ic):200mA;功率(Pd):150mW;直流电流增益(hFE@Ic,Vce):100@10mA,1V;")
      (fields (field (name "Manufacturer") "LRC(乐山无线电)"))
      (libsource (lib "easyedapro") (part "LMBT3904DW1T1G"))
    )
    (comp (ref "Q2")
      (value "SI2301CDS-T1-GE3-ES")
      (footprint "easyedapro:SOT-23-3_L2.9-W1.3-P1.90-LS2.4-BR")
      (description "类型:P沟道;漏源电压(Vdss):20V;连续漏极电流(Id):3A;功率(Pd):1W;导通电阻(RDS(on)@Vgs,Id):58mΩ@4.5V,3A;")
      (fields (field (name "Manufacturer") "ElecSuper(静芯微）"))
      (libsource (lib "easyedapro") (part "SI2301CDS-T1-GE3-ES"))
    )
    (comp (ref "R11")
      (value "5.1kΩ")
      (footprint "easyedapro:R0402")
      (description "电阻类型:厚膜电阻;阻值:5.1kΩ;精度:±1%;功率:62.5mW;温度系数:±100ppm/°C;")
      (fields
        (field (name "Manufacturer Part") "0402WGF5101TCE")
        (field (name "Manufacturer") "UNI-ROYAL(厚声)")
      )
      (libsource (lib "easyedapro") (part "0402WGF5101TCE"))
    )
    (comp (ref "R12")
      (value "5.1kΩ")
      (footprint "easyedapro:R0402")
      (description "电阻类型:厚膜电阻;阻值:5.1kΩ;精度:±1%;功率:62.5mW;温度系数:±100ppm/°C;")
      (fields
        (field (name "Manufacturer Part") "0402WGF5101TCE")
        (field (name "Manufacturer") "UNI-ROYAL(厚声)")
      )
      (libsource (lib "easyedapro") (part "0402WGF5101TCE"))
    )
    (comp (ref "R13")
      (value "10kΩ")
      (footprint "easyedapro:R0402")
      (description "电阻类型:厚膜电阻;阻值:10kΩ;精度:±1%;功率:62.5mW;温度系数:±100ppm/°C;")
      (fields
        (field (name "Manufacturer Part") "0402WGF1002TCE")
        (field (name "Manufacturer") "UNI-ROYAL(厚声)")
      )
      (libsource (lib "easyedapro") (part "0402WGF1002TCE"))
    )
    (comp (ref "R14")
      (value "10kΩ")
      (footprint "easyedapro:R0402")
      (description "电阻类型:厚膜电阻;阻值:10kΩ;精度:±1%;功率:62.5mW;温度系数:±100ppm/°C;")
      (fields
        (field (name "Manufacturer Part") "0402WGF1002TCE")
        (field (name "Manufacturer") "UNI-ROYAL(厚声)")
      )
      (libsource (lib "easyedapro") (part "0402WGF1002TCE"))
    )
    (comp (ref "R15")
      (value "10kΩ")
      (footprint "easyedapro:R0402")
      (description "电阻类型:厚膜电阻;阻值:10kΩ;精度:±1%;功率:62.5mW;温度系数:±100ppm/°C;")
      (fields
        (field (name "Manufacturer Part") "0402WGF1002TCE")
        (field (name "Manufacturer") "UNI-ROYAL(厚声)")
      )
      (libsource (lib "easyedapro") (part "0402WGF1002TCE"))
    )
    (comp (ref "R16")
      (value "10kΩ")
      (footprint "easyedapro:R0402")
      (description "电阻类型:厚膜电阻;阻值:10kΩ;精度:±1%;功率:62.5mW;温度系数:±100ppm/°C;")
      (fields
        (field (name "Manufacturer Part") "0402WGF1002TCE")
        (field (name "Manufacturer") "UNI-ROYAL(厚声)")
      )
      (libsource (lib "easyedapro") (part "0402WGF1002TCE"))
    )
    (comp (ref "R17")
      (value "680kΩ")
      (footprint "easyedapro:R0402")
      (description "电阻类型:厚膜电阻;阻值:680kΩ;精度:±1%;功率:62.5mW;最大工作电压:50V;温度系数:±100ppm/°C;")
      (fields
        (field (name "Manufacturer Part") "0402WGF6803TCE")
        (field (name "Manufacturer") "UNI-ROYAL(厚声)")
      )
      (libsource (lib "easyedapro") (part "0402WGF6803TCE"))
    )
    (comp (ref "R18")
      (value "150kΩ")
      (footprint "easyedapro:R0402")
      (description "电阻类型:厚膜电阻;阻值:150kΩ;精度:±1%;功率:62.5mW;最大工作电压:50V;温度系数:±100ppm/°C;")
      (fields
        (field (name "Manufacturer Part") "0402WGF1503TCE")
        (field (name "Manufacturer") "UNI-ROYAL(厚声)")
      )
      (libsource (lib "easyedapro") (part "0402WGF1503TCE"))
    )
    (comp (ref "R19")
      (value "10kΩ")
      (footprint "easyedapro:R0402")
      (description "电阻类型:厚膜电阻;阻值:10kΩ;精度:±1%;功率:62.5mW;温度系数:±100ppm/°C;")
      (fields
        (field (name "Manufacturer Part") "0402WGF1002TCE")
        (field (name "Manufacturer") "UNI-ROYAL(厚声)")
      )
      (libsource (lib "easyedapro") (part "0402WGF1002TCE"))
    )
    (comp (ref "R20")
      (value "10Ω")
      (footprint "easyedapro:R0402")
      (description "电阻类型:厚膜电阻;阻值:10Ω;精度:±1%;功率:62.5mW;温度系数:±200ppm/°C;")
      (fields
        (field (name "Manufacturer Part") "0402WGF100JTCE")
        (field (name "Manufacturer") "UNI-ROYAL(厚声)")
      )
      (libsource (lib "easyedapro") (part "0402WGF100JTCE"))
    )
    (comp (ref "R21")
      (value "10kΩ")
      (footprint "easyedapro:R0402")
      (description "电阻类型:厚膜电阻;阻值:10kΩ;精度:±1%;功率:62.5mW;温度系数:±100ppm/°C;")
      (fields
        (field (name "Manufacturer Part") "0402WGF1002TCE")
        (field (name "Manufacturer") "UNI-ROYAL(厚声)")
      )
      (libsource (lib "easyedapro") (part "0402WGF1002TCE"))
    )
    (comp (ref "R22")
      (value "680kΩ")
      (footprint "easyedapro:R0402")
      (description "电阻类型:厚膜电阻;阻值:680kΩ;精度:±1%;功率:62.5mW;最大工作电压:50V;温度系数:±100ppm/°C;")
      (fields
        (field (name "Manufacturer Part") "0402WGF6803TCE")
        (field (name "Manufacturer") "UNI-ROYAL(厚声)")
      )
      (libsource (lib "easyedapro") (part "0402WGF6803TCE"))
    )
    (comp (ref "R23")
      (value "1kΩ")
      (footprint "easyedapro:R0402")
      (description "电阻类型:厚膜电阻;阻值:1kΩ;精度:±1%;功率:62.5mW;")
      (fields
        (field (name "Manufacturer Part") "0402WGF1001TCE")
        (field (name "Manufacturer") "UNI-ROYAL(厚声)")
      )
      (libsource (lib "easyedapro") (part "0402WGF1001TCE"))
    )
    (comp (ref "R24")
      (value "150kΩ")
      (footprint "easyedapro:R0402")
      (description "电阻类型:厚膜电阻;阻值:150kΩ;精度:±1%;功率:62.5mW;最大工作电压:50V;温度系数:±100ppm/°C;")
      (fields
        (field (name "Manufacturer Part") "0402WGF1503TCE")
        (field (name "Manufacturer") "UNI-ROYAL(厚声)")
      )
      (libsource (lib "easyedapro") (part "0402WGF1503TCE"))
    )
    (comp (ref "R25")
      (value "10kΩ")
      (footprint "easyedapro:R0402")
      (description "电阻类型:厚膜电阻;阻值:10kΩ;精度:±1%;功率:62.5mW;温度系数:±100ppm/°C;")
      (fields
        (field (name "Manufacturer Part") "0402WGF1002TCE")
        (field (name "Manufacturer") "UNI-ROYAL(厚声)")
      )
      (libsource (lib "easyedapro") (part "0402WGF1002TCE"))
    )
    (comp (ref "U4")
      (value "CH340K")
      (footprint "easyedapro:ESOP-10_L4.9-W3.9-P1.00-LS6.0-BL-EP")
      (fields (field (name "Manufacturer") "WCH(南京沁恒)"))
      (libsource (lib "easyedapro") (part "CH340K_C18208922"))
    )
    (comp (ref "U5")
      (value "CH334F")
      (footprint "easyedapro:QFN-24_L4.0-W4.0-P0.50-BL-EP2.8")
      (fields (field (name "Manufacturer") "WCH(南京沁恒)"))
      (libsource (lib "easyedapro") (part "CH334F_C5187527"))
    )
    (comp (ref "U6")
      (value "SY8088AAC")
      (footprint "easyedapro:SOT-23-5_L3.0-W1.7-P0.95-LS2.8-BR")
      (description "功能类型:降压型;输入电压:-;输出电流(最大值):-;")
      (fields (field (name "Manufacturer") "silergy(矽力杰)"))
      (libsource (lib "easyedapro") (part "SY8088AAC"))
    )
    (comp (ref "U7")
      (value "ME6211C28M5G-N")
      (footprint "easyedapro:SOT-23-5_L3.0-W1.7-P0.95-LS2.8-BR")
      (description "输出类型:固定;最大输入电压:6V;输出电压:2.8V;最大输出电流:450mA;电源纹波抑制比(PSRR):70dB@(1kHz);输出极性:正极;")
      (fields (field (name "Manufacturer") "MICRONE(南京微盟)"))
      (libsource (lib "easyedapro") (part "ME6211C28M5G-N"))
    )
    (comp (ref "U8")
      (value "SY8088AAC")
      (footprint "easyedapro:SOT-23-5_L3.0-W1.7-P0.95-LS2.8-BR")
      (description "功能类型:降压型;输入电压:-;输出电流(最大值):-;")
      (fields (field (name "Manufacturer") "silergy(矽力杰)"))
      (libsource (lib "easyedapro") (part "SY8088AAC"))
    )
    (comp (ref "USB1")
      (value "TYPEC-304-ACP16")
      (footprint "easyedapro:USB-C-SMD_TYPE-C-16P-1")
      (fields (field (name "Manufacturer") "XUNPU(讯普)"))
      (libsource (lib "easyedapro") (part "TYPEC-304-ACP16"))
    )
    (comp (ref "X1")
      (value "12MHz")
      (footprint "easyedapro:OSC-SMD_4P-L3.2-W2.5-BL")
      (description "晶振类型:贴片晶振;频率:12MHz;常温频差:±10ppm;外接负载电容:20pF;频率稳定度(全温):±20ppm;")
      (fields (field (name "Manufacturer Part") "X322512MSB4SI") (field (name "Manufacturer") "YXC(扬兴晶振)"))
      (libsource (lib "easyedapro") (part "X322512MSB4SI"))
    )
    (comp (ref "C34")
      (value "1uF")
      (footprint "easyedapro:C0402")
      (description "容值:1uF;精度:±10%;额定电压:25V;材质(温度系数):X5R;")
      (fields
        (field (name "Manufacturer Part") "CL05A105KA5NQNC")
        (field (name "Manufacturer") "SAMSUNG(三星)")
      )
      (libsource (lib "easyedapro") (part "CL05A105KA5NQNC"))
    )
    (comp (ref "C35")
      (value "1uF")
      (footprint "easyedapro:C0402")
      (description "容值:1uF;精度:±10%;额定电压:25V;材质(温度系数):X5R;")
      (fields
        (field (name "Manufacturer Part") "CL05A105KA5NQNC")
        (field (name "Manufacturer") "SAMSUNG(三星)")
      )
      (libsource (lib "easyedapro") (part "CL05A105KA5NQNC"))
    )
    (comp (ref "C36")
      (value "1uF")
      (footprint "easyedapro:C0402")
      (description "容值:1uF;精度:±10%;额定电压:25V;材质(温度系数):X5R;")
      (fields
        (field (name "Manufacturer Part") "CL05A105KA5NQNC")
        (field (name "Manufacturer") "SAMSUNG(三星)")
      )
      (libsource (lib "easyedapro") (part "CL05A105KA5NQNC"))
    )
    (comp (ref "C37")
      (value "1uF")
      (footprint "easyedapro:C0402")
      (description "容值:1uF;精度:±10%;额定电压:25V;材质(温度系数):X5R;")
      (fields
        (field (name "Manufacturer Part") "CL05A105KA5NQNC")
        (field (name "Manufacturer") "SAMSUNG(三星)")
      )
      (libsource (lib "easyedapro") (part "CL05A105KA5NQNC"))
    )
    (comp (ref "C38")
      (value "1uF")
      (footprint "easyedapro:C0402")
      (description "容值:1uF;精度:±10%;额定电压:25V;材质(温度系数):X5R;")
      (fields
        (field (name "Manufacturer Part") "CL05A105KA5NQNC")
        (field (name "Manufacturer") "SAMSUNG(三星)")
      )
      (libsource (lib "easyedapro") (part "CL05A105KA5NQNC"))
    )
    (comp (ref "C39")
      (value "1uF")
      (footprint "easyedapro:C0402")
      (description "容值:1uF;精度:±10%;额定电压:25V;材质(温度系数):X5R;")
      (fields
        (field (name "Manufacturer Part") "CL05A105KA5NQNC")
        (field (name "Manufacturer") "SAMSUNG(三星)")
      )
      (libsource (lib "easyedapro") (part "CL05A105KA5NQNC"))
    )
    (comp (ref "C40")
      (value "1uF")
      (footprint "easyedapro:C0402")
      (description "容值:1uF;精度:±10%;额定电压:25V;材质(温度系数):X5R;")
      (fields
        (field (name "Manufacturer Part") "CL05A105KA5NQNC")
        (field (name "Manufacturer") "SAMSUNG(三星)")
      )
      (libsource (lib "easyedapro") (part "CL05A105KA5NQNC"))
    )
    (comp (ref "C41")
      (value "1uF")
      (footprint "easyedapro:C0402")
      (description "容值:1uF;精度:±10%;额定电压:25V;材质(温度系数):X5R;")
      (fields
        (field (name "Manufacturer Part") "CL05A105KA5NQNC")
        (field (name "Manufacturer") "SAMSUNG(三星)")
      )
      (libsource (lib "easyedapro") (part "CL05A105KA5NQNC"))
    )
    (comp (ref "C42")
      (value "1uF")
      (footprint "easyedapro:C0402")
      (description "容值:1uF;精度:±10%;额定电压:25V;材质(温度系数):X5R;")
      (fields
        (field (name "Manufacturer Part") "CL05A105KA5NQNC")
        (field (name "Manufacturer") "SAMSUNG(三星)")
      )
      (libsource (lib "easyedapro") (part "CL05A105KA5NQNC"))
    )
    (comp (ref "C43")
      (value "1uF")
      (footprint "easyedapro:C0402")
      (description "容值:1uF;精度:±10%;额定电压:25V;材质(温度系数):X5R;")
      (fields
        (field (name "Manufacturer Part") "CL05A105KA5NQNC")
        (field (name "Manufacturer") "SAMSUNG(三星)")
      )
      (libsource (lib "easyedapro") (part "CL05A105KA5NQNC"))
    )
    (comp (ref "C44")
      (value "1uF")
      (footprint "easyedapro:C0402")
      (description "容值:1uF;精度:±10%;额定电压:25V;材质(温度系数):X5R;")
      (fields
        (field (name "Manufacturer Part") "CL05A105KA5NQNC")
        (field (name "Manufacturer") "SAMSUNG(三星)")
      )
      (libsource (lib "easyedapro") (part "CL05A105KA5NQNC"))
    )
    (comp (ref "C45")
      (value "1uF")
      (footprint "easyedapro:C0402")
      (description "容值:1uF;精度:±10%;额定电压:25V;材质(温度系数):X5R;")
      (fields
        (field (name "Manufacturer Part") "CL05A105KA5NQNC")
        (field (name "Manufacturer") "SAMSUNG(三星)")
      )
      (libsource (lib "easyedapro") (part "CL05A105KA5NQNC"))
    )
    (comp (ref "C46")
      (value "1uF")
      (footprint "easyedapro:C0402")
      (description "容值:1uF;精度:±10%;额定电压:25V;材质(温度系数):X5R;")
      (fields
        (field (name "Manufacturer Part") "CL05A105KA5NQNC")
        (field (name "Manufacturer") "SAMSUNG(三星)")
      )
      (libsource (lib "easyedapro") (part "CL05A105KA5NQNC"))
    )
    (comp (ref "C47")
      (value "1uF")
      (footprint "easyedapro:C0402")
      (description "容值:1uF;精度:±10%;额定电压:25V;材质(温度系数):X5R;")
      (fields
        (field (name "Manufacturer Part") "CL05A105KA5NQNC")
        (field (name "Manufacturer") "SAMSUNG(三星)")
      )
      (libsource (lib "easyedapro") (part "CL05A105KA5NQNC"))
    )
    (comp (ref "C48")
      (value "1uF")
      (footprint "easyedapro:C0402")
      (description "容值:1uF;精度:±10%;额定电压:25V;材质(温度系数):X5R;")
      (fields
        (field (name "Manufacturer Part") "CL05A105KA5NQNC")
        (field (name "Manufacturer") "SAMSUNG(三星)")
      )
      (libsource (lib "easyedapro") (part "CL05A105KA5NQNC"))
    )
    (comp (ref "C49")
      (value "1uF")
      (footprint "easyedapro:C0402")
      (description "容值:1uF;精度:±10%;额定电压:25V;材质(温度系数):X5R;")
      (fields
        (field (name "Manufacturer Part") "CL05A105KA5NQNC")
        (field (name "Manufacturer") "SAMSUNG(三星)")
      )
      (libsource (lib "easyedapro") (part "CL05A105KA5NQNC"))
    )
    (comp (ref "C50")
      (value "100nF")
      (footprint "easyedapro:C0402")
      (description "温度系数:X7R;容值:100nF;精度:±10%;额定电压:50V;")
      (fields (field (name "Manufacturer Part") "0402B104K500NT") (field (name "Manufacturer") "FH(风华)"))
      (libsource (lib "easyedapro") (part "0402B104K500NT"))
    )
    (comp (ref "C51")
      (value "100nF")
      (footprint "easyedapro:C0402")
      (description "温度系数:X7R;容值:100nF;精度:±10%;额定电压:50V;")
      (fields (field (name "Manufacturer Part") "0402B104K500NT") (field (name "Manufacturer") "FH(风华)"))
      (libsource (lib "easyedapro") (part "0402B104K500NT"))
    )
    (comp (ref "C52")
      (value "1uF")
      (footprint "easyedapro:C0402")
      (description "容值:1uF;精度:±10%;额定电压:25V;材质(温度系数):X5R;")
      (fields
        (field (name "Manufacturer Part") "CL05A105KA5NQNC")
        (field (name "Manufacturer") "SAMSUNG(三星)")
      )
      (libsource (lib "easyedapro") (part "CL05A105KA5NQNC"))
    )
    (comp (ref "C53")
      (value "22pF")
      (footprint "easyedapro:C0402")
      (description "容值:22pF;精度:±5%;额定电压:50V;材质(温度系数):C0G;")
      (fields (field (name "Manufacturer Part") "0402CG220J500NT") (field (name "Manufacturer") "FH(风华)"))
      (libsource (lib "easyedapro") (part "0402CG220J500NT"))
    )
    (comp (ref "C54")
      (value "22pF")
      (footprint "easyedapro:C0402")
      (description "容值:22pF;精度:±5%;额定电压:50V;材质(温度系数):C0G;")
      (fields (field (name "Manufacturer Part") "0402CG220J500NT") (field (name "Manufacturer") "FH(风华)"))
      (libsource (lib "easyedapro") (part "0402CG220J500NT"))
    )
    (comp (ref "C55")
      (value "1uF")
      (footprint "easyedapro:C0402")
      (description "容值:1uF;精度:±10%;额定电压:25V;材质(温度系数):X5R;")
      (fields
        (field (name "Manufacturer Part") "CL05A105KA5NQNC")
        (field (name "Manufacturer") "SAMSUNG(三星)")
      )
      (libsource (lib "easyedapro") (part "CL05A105KA5NQNC"))
    )
    (comp (ref "C56")
      (value "100nF")
      (footprint "easyedapro:C0402")
      (description "温度系数:X7R;容值:100nF;精度:±10%;额定电压:50V;")
      (fields (field (name "Manufacturer Part") "0402B104K500NT") (field (name "Manufacturer") "FH(风华)"))
      (libsource (lib "easyedapro") (part "0402B104K500NT"))
    )
    (comp (ref "C57")
      (value "100nF")
      (footprint "easyedapro:C0402")
      (description "温度系数:X7R;容值:100nF;精度:±10%;额定电压:50V;")
      (fields (field (name "Manufacturer Part") "0402B104K500NT") (field (name "Manufacturer") "FH(风华)"))
      (libsource (lib "easyedapro") (part "0402B104K500NT"))
    )
    (comp (ref "C58")
      (value "1uF")
      (footprint "easyedapro:C0402")
      (description "容值:1uF;精度:±10%;额定电压:25V;材质(温度系数):X5R;")
      (fields
        (field (name "Manufacturer Part") "CL05A105KA5NQNC")
        (field (name "Manufacturer") "SAMSUNG(三星)")
      )
      (libsource (lib "easyedapro") (part "CL05A105KA5NQNC"))
    )
    (comp (ref "C59")
      (value "1uF")
      (footprint "easyedapro:C0402")
      (description "容值:1uF;精度:±10%;额定电压:25V;材质(温度系数):X5R;")
      (fields
        (field (name "Manufacturer Part") "CL05A105KA5NQNC")
        (field (name "Manufacturer") "SAMSUNG(三星)")
      )
      (libsource (lib "easyedapro") (part "CL05A105KA5NQNC"))
    )
    (comp (ref "C60")
      (value "1uF")
      (footprint "easyedapro:C0402")
      (description "容值:1uF;精度:±10%;额定电压:25V;材质(温度系数):X5R;")
      (fields
        (field (name "Manufacturer Part") "CL05A105KA5NQNC")
        (field (name "Manufacturer") "SAMSUNG(三星)")
      )
      (libsource (lib "easyedapro") (part "CL05A105KA5NQNC"))
    )
    (comp (ref "C61")
      (value "1uF")
      (footprint "easyedapro:C0402")
      (description "容值:1uF;精度:±10%;额定电压:25V;材质(温度系数):X5R;")
      (fields
        (field (name "Manufacturer Part") "CL05A105KA5NQNC")
        (field (name "Manufacturer") "SAMSUNG(三星)")
      )
      (libsource (lib "easyedapro") (part "CL05A105KA5NQNC"))
    )
    (comp (ref "C62")
      (value "22pF")
      (footprint "easyedapro:C0402")
      (description "容值:22pF;精度:±5%;额定电压:50V;材质(温度系数):C0G;")
      (fields (field (name "Manufacturer Part") "0402CG220J500NT") (field (name "Manufacturer") "FH(风华)"))
      (libsource (lib "easyedapro") (part "0402CG220J500NT"))
    )
    (comp (ref "C63")
      (value "22pF")
      (footprint "easyedapro:C0402")
      (description "容值:22pF;精度:±5%;额定电压:50V;材质(温度系数):C0G;")
      (fields (field (name "Manufacturer Part") "0402CG220J500NT") (field (name "Manufacturer") "FH(风华)"))
      (libsource (lib "easyedapro") (part "0402CG220J500NT"))
    )
    (comp (ref "C64")
      (value "22pF")
      (footprint "easyedapro:C0402")
      (description "容值:22pF;精度:±5%;额定电压:50V;材质(温度系数):C0G;")
      (fields (field (name "Manufacturer Part") "0402CG220J500NT") (field (name "Manufacturer") "FH(风华)"))
      (libsource (lib "easyedapro") (part "0402CG220J500NT"))
    )
    (comp (ref "C65")
      (value "1uF")
      (footprint "easyedapro:C0402")
      (description "容值:1uF;精度:±10%;额定电压:25V;材质(温度系数):X5R;")
      (fields
        (field (name "Manufacturer Part") "CL05A105KA5NQNC")
        (field (name "Manufacturer") "SAMSUNG(三星)")
      )
      (libsource (lib "easyedapro") (part "CL05A105KA5NQNC"))
    )
    (comp (ref "C66")
      (value "1uF")
      (footprint "easyedapro:C0402")
      (description "容值:1uF;精度:±10%;额定电压:25V;材质(温度系数):X5R;")
      (fields
        (field (name "Manufacturer Part") "CL05A105KA5NQNC")
        (field (name "Manufacturer") "SAMSUNG(三星)")
      )
      (libsource (lib "easyedapro") (part "CL05A105KA5NQNC"))
    )
    (comp (ref "C67")
      (value "22pF")
      (footprint "easyedapro:C0402")
      (description "容值:22pF;精度:±5%;额定电压:50V;材质(温度系数):C0G;")
      (fields (field (name "Manufacturer Part") "0402CG220J500NT") (field (name "Manufacturer") "FH(风华)"))
      (libsource (lib "easyedapro") (part "0402CG220J500NT"))
    )
    (comp (ref "C68")
      (value "22pF")
      (footprint "easyedapro:C0402")
      (description "容值:22pF;精度:±5%;额定电压:50V;材质(温度系数):C0G;")
      (fields (field (name "Manufacturer Part") "0402CG220J500NT") (field (name "Manufacturer") "FH(风华)"))
      (libsource (lib "easyedapro") (part "0402CG220J500NT"))
    )
    (comp (ref "C69")
      (value "22pF")
      (footprint "easyedapro:C0402")
      (description "容值:22pF;精度:±5%;额定电压:50V;材质(温度系数):C0G;")
      (fields (field (name "Manufacturer Part") "0402CG220J500NT") (field (name "Manufacturer") "FH(风华)"))
      (libsource (lib "easyedapro") (part "0402CG220J500NT"))
    )
    (comp (ref "C70")
      (value "1nF")
      (footprint "easyedapro:C0402")
      (description "容值:1nF;精度:±10%;额定电压:50V;材质(温度系数):X7R;")
      (fields (field (name "Manufacturer Part") "0402B102K500NT") (field (name "Manufacturer") "FH(风华)"))
      (libsource (lib "easyedapro") (part "0402B102K500NT"))
    )
    (comp (ref "C71")
      (value "1nF")
      (footprint "easyedapro:C0402")
      (description "容值:1nF;精度:±10%;额定电压:50V;材质(温度系数):X7R;")
      (fields (field (name "Manufacturer Part") "0402B102K500NT") (field (name "Manufacturer") "FH(风华)"))
      (libsource (lib "easyedapro") (part "0402B102K500NT"))
    )
    (comp (ref "C72")
      (value "100nF")
      (footprint "easyedapro:C0402")
      (description "容值:100nF;精度:±10%;额定电压:16V;材质(温度系数):X7R;")
      (fields
        (field (name "Manufacturer Part") "CL05B104KO5NNNC")
        (field (name "Manufacturer") "SAMSUNG(三星)")
      )
      (libsource (lib "easyedapro") (part "CL05B104KO5NNNC"))
    )
    (comp (ref "C73")
      (value "100nF")
      (footprint "easyedapro:C0402")
      (description "容值:100nF;精度:±10%;额定电压:16V;材质(温度系数):X7R;")
      (fields
        (field (name "Manufacturer Part") "CL05B104KO5NNNC")
        (field (name "Manufacturer") "SAMSUNG(三星)")
      )
      (libsource (lib "easyedapro") (part "CL05B104KO5NNNC"))
    )
    (comp (ref "C74")
      (value "1uF")
      (footprint "easyedapro:C0402")
      (description "容值:1uF;精度:±10%;额定电压:25V;材质(温度系数):X5R;")
      (fields
        (field (name "Manufacturer Part") "CL05A105KA5NQNC")
        (field (name "Manufacturer") "SAMSUNG(三星)")
      )
      (libsource (lib "easyedapro") (part "CL05A105KA5NQNC"))
    )
    (comp (ref "C75")
      (value "22uF")
      (footprint "easyedapro:C0603")
      (description "容值:22uF;精度:±20%;额定电压:16V;材质(温度系数):X5R;")
      (fields
        (field (name "Manufacturer Part") "CL10A226MO7JZNC")
        (field (name "Manufacturer") "SAMSUNG(三星)")
      )
      (libsource (lib "easyedapro") (part "CL10A226MO7JZNC"))
    )
    (comp (ref "C76")
      (value "22uF")
      (footprint "easyedapro:C0603")
      (description "容值:22uF;精度:±20%;额定电压:16V;材质(温度系数):X5R;")
      (fields
        (field (name "Manufacturer Part") "CL10A226MO7JZNC")
        (field (name "Manufacturer") "SAMSUNG(三星)")
      )
      (libsource (lib "easyedapro") (part "CL10A226MO7JZNC"))
    )
    (comp (ref "C77")
      (value "22pF")
      (footprint "easyedapro:C0402")
      (description "容值:22pF;精度:±5%;额定电压:50V;材质(温度系数):C0G;")
      (fields (field (name "Manufacturer Part") "0402CG220J500NT") (field (name "Manufacturer") "FH(风华)"))
      (libsource (lib "easyedapro") (part "0402CG220J500NT"))
    )
    (comp (ref "C78")
      (value "22pF")
      (footprint "easyedapro:C0402")
      (description "容值:22pF;精度:±5%;额定电压:50V;材质(温度系数):C0G;")
      (fields (field (name "Manufacturer Part") "0402CG220J500NT") (field (name "Manufacturer") "FH(风华)"))
      (libsource (lib "easyedapro") (part "0402CG220J500NT"))
    )
    (comp (ref "C79")
      (value "1uF")
      (footprint "easyedapro:C0402")
      (description "容值:1uF;精度:±10%;额定电压:25V;材质(温度系数):X5R;")
      (fields
        (field (name "Manufacturer Part") "CL05A105KA5NQNC")
        (field (name "Manufacturer") "SAMSUNG(三星)")
      )
      (libsource (lib "easyedapro") (part "CL05A105KA5NQNC"))
    )
    (comp (ref "C80")
      (value "100nF")
      (footprint "easyedapro:C0402")
      (description "温度系数:X7R;容值:100nF;精度:±10%;额定电压:50V;")
      (fields (field (name "Manufacturer Part") "0402B104K500NT") (field (name "Manufacturer") "FH(风华)"))
      (libsource (lib "easyedapro") (part "0402B104K500NT"))
    )
    (comp (ref "C81")
      (value "10uF")
      (footprint "easyedapro:C0402")
      (description "容值:10uF;精度:±20%;额定电压:6.3V;材质(温度系数):X5R;")
      (fields
        (field (name "Manufacturer Part") "CL05A106MQ5NUNC")
        (field (name "Manufacturer") "SAMSUNG(三星)")
      )
      (libsource (lib "easyedapro") (part "CL05A106MQ5NUNC"))
    )
    (comp (ref "C82")
      (value "22pF")
      (footprint "easyedapro:C0402")
      (description "容值:22pF;精度:±5%;额定电压:50V;材质(温度系数):C0G;")
      (fields (field (name "Manufacturer Part") "0402CG220J500NT") (field (name "Manufacturer") "FH(风华)"))
      (libsource (lib "easyedapro") (part "0402CG220J500NT"))
    )
    (comp (ref "C83")
      (value "100nF")
      (footprint "easyedapro:C0402")
      (description "温度系数:X7R;容值:100nF;精度:±10%;额定电压:50V;")
      (fields (field (name "Manufacturer Part") "0402B104K500NT") (field (name "Manufacturer") "FH(风华)"))
      (libsource (lib "easyedapro") (part "0402B104K500NT"))
    )
    (comp (ref "C84")
      (value "10uF")
      (footprint "easyedapro:C0402")
      (description "容值:10uF;精度:±20%;额定电压:6.3V;材质(温度系数):X5R;")
      (fields
        (field (name "Manufacturer Part") "CL05A106MQ5NUNC")
        (field (name "Manufacturer") "SAMSUNG(三星)")
      )
      (libsource (lib "easyedapro") (part "CL05A106MQ5NUNC"))
    )
    (comp (ref "C85")
      (value "22pF")
      (footprint "easyedapro:C0402")
      (description "容值:22pF;精度:±5%;额定电压:50V;材质(温度系数):C0G;")
      (fields (field (name "Manufacturer Part") "0402CG220J500NT") (field (name "Manufacturer") "FH(风华)"))
      (libsource (lib "easyedapro") (part "0402CG220J500NT"))
    )
    (comp (ref "J7")
      (value "X9821WRS-02-9TSN")
      (footprint "easyedapro:CONN-SMD_2P-P1.25_X9821WRS-02-9TSN")
      (fields (field (name "Manufacturer") "XKB Connectivity(中国星坤)"))
      (libsource (lib "easyedapro") (part "X9821WRS-02-9TSN"))
    )
    (comp (ref "MIC1")
      (value "ZTS6216")
      (footprint "easyedapro:MIC-SMD_4P-L2.8-W1.9-P1.84-TL")
      (description "方向:全指向;灵敏度:-38dB;信噪比:65dB;电流消耗:120uA;电源电压:1.5V~3.6V;阻抗:100Ω;")
      (fields (field (name "Manufacturer") "ZILLTEK(钰太)"))
      (libsource (lib "easyedapro") (part "ZTS6216"))
    )
    (comp (ref "MIC2")
      (value "ZTS6216")
      (footprint "easyedapro:MIC-SMD_4P-L2.8-W1.9-P1.84-TL")
      (description "方向:全指向;灵敏度:-38dB;信噪比:65dB;电流消耗:120uA;电源电压:1.5V~3.6V;阻抗:100Ω;")
      (fields (field (name "Manufacturer") "ZILLTEK(钰太)"))
      (libsource (lib "easyedapro") (part "ZTS6216"))
    )
    (comp (ref "R26")
      (value "10kΩ")
      (footprint "easyedapro:R0402")
      (description "电阻类型:厚膜电阻;阻值:10kΩ;精度:±1%;功率:62.5mW;温度系数:±100ppm/°C;")
      (fields
        (field (name "Manufacturer Part") "0402WGF1002TCE")
        (field (name "Manufacturer") "UNI-ROYAL(厚声)")
      )
      (libsource (lib "easyedapro") (part "0402WGF1002TCE"))
    )
    (comp (ref "R27")
      (value "10kΩ")
      (footprint "easyedapro:R0402")
      (description "电阻类型:厚膜电阻;阻值:10kΩ;精度:±1%;功率:62.5mW;温度系数:±100ppm/°C;")
      (fields
        (field (name "Manufacturer Part") "0402WGF1002TCE")
        (field (name "Manufacturer") "UNI-ROYAL(厚声)")
      )
      (libsource (lib "easyedapro") (part "0402WGF1002TCE"))
    )
    (comp (ref "R28")
      (value "0Ω")
      (footprint "easyedapro:R0402")
      (description "电阻类型:厚膜电阻;阻值:0Ω;精度:±1%;功率:62.5mW;")
      (fields
        (field (name "Manufacturer Part") "0402WGF0000TCE")
        (field (name "Manufacturer") "UNI-ROYAL(厚声)")
      )
      (libsource (lib "easyedapro") (part "0402WGF0000TCE"))
    )
    (comp (ref "R29")
      (value "0Ω")
      (footprint "easyedapro:R0402")
      (description "电阻类型:厚膜电阻;阻值:0Ω;精度:±1%;功率:62.5mW;")
      (fields
        (field (name "Manufacturer Part") "0402WGF0000TCE")
        (field (name "Manufacturer") "UNI-ROYAL(厚声)")
      )
      (libsource (lib "easyedapro") (part "0402WGF0000TCE"))
    )
    (comp (ref "R30")
      (value "0Ω")
      (footprint "easyedapro:R0402")
      (description "电阻类型:厚膜电阻;阻值:0Ω;精度:±1%;功率:62.5mW;")
      (fields
        (field (name "Manufacturer Part") "0402WGF0000TCE")
        (field (name "Manufacturer") "UNI-ROYAL(厚声)")
      )
      (libsource (lib "easyedapro") (part "0402WGF0000TCE"))
    )
    (comp (ref "R31")
      (value "0Ω")
      (footprint "easyedapro:R0402")
      (description "电阻类型:厚膜电阻;阻值:0Ω;精度:±1%;功率:62.5mW;")
      (fields
        (field (name "Manufacturer Part") "0402WGF0000TCE")
        (field (name "Manufacturer") "UNI-ROYAL(厚声)")
      )
      (libsource (lib "easyedapro") (part "0402WGF0000TCE"))
    )
    (comp (ref "R32")
      (value "0Ω")
      (footprint "easyedapro:R0402")
      (description "电阻类型:厚膜电阻;阻值:0Ω;精度:±1%;功率:62.5mW;")
      (fields
        (field (name "Manufacturer Part") "0402WGF0000TCE")
        (field (name "Manufacturer") "UNI-ROYAL(厚声)")
      )
      (libsource (lib "easyedapro") (part "0402WGF0000TCE"))
    )
    (comp (ref "R33")
      (value "0Ω")
      (footprint "easyedapro:R0402")
      (description "电阻类型:厚膜电阻;阻值:0Ω;精度:±1%;功率:62.5mW;")
      (fields
        (field (name "Manufacturer Part") "0402WGF0000TCE")
        (field (name "Manufacturer") "UNI-ROYAL(厚声)")
      )
      (libsource (lib "easyedapro") (part "0402WGF0000TCE"))
    )
    (comp (ref "R34")
      (value "0Ω")
      (footprint "easyedapro:R0402")
      (description "电阻类型:厚膜电阻;阻值:0Ω;精度:±1%;功率:62.5mW;")
      (fields
        (field (name "Manufacturer Part") "0402WGF0000TCE")
        (field (name "Manufacturer") "UNI-ROYAL(厚声)")
      )
      (libsource (lib "easyedapro") (part "0402WGF0000TCE"))
    )
    (comp (ref "R35")
      (value "0Ω")
      (footprint "easyedapro:R0402")
      (description "电阻类型:厚膜电阻;阻值:0Ω;精度:±1%;功率:62.5mW;")
      (fields
        (field (name "Manufacturer Part") "0402WGF0000TCE")
        (field (name "Manufacturer") "UNI-ROYAL(厚声)")
      )
      (libsource (lib "easyedapro") (part "0402WGF0000TCE"))
    )
    (comp (ref "R36")
      (value "51Ω")
      (footprint "easyedapro:R0402")
      (description "电阻类型:厚膜电阻;阻值:51Ω;精度:±1%;功率:62.5mW;最大工作电压:50V;温度系数:±100ppm/°C;")
      (fields
        (field (name "Manufacturer Part") "0402WGF510JTCE")
        (field (name "Manufacturer") "UNI-ROYAL(厚声)")
      )
      (libsource (lib "easyedapro") (part "0402WGF510JTCE"))
    )
    (comp (ref "R37")
      (value "0Ω(NC)")
      (footprint "easyedapro:R0402")
      (description "电阻类型:厚膜电阻;阻值:0Ω;精度:±1%;功率:62.5mW;")
      (fields
        (field (name "Manufacturer Part") "0402WGF0000TCE")
        (field (name "Manufacturer") "UNI-ROYAL(厚声)")
      )
      (libsource (lib "easyedapro") (part "0402WGF0000TCE"))
    )
    (comp (ref "R38")
      (value "0Ω")
      (footprint "easyedapro:R0402")
      (description "电阻类型:厚膜电阻;阻值:0Ω;精度:±1%;功率:62.5mW;")
      (fields
        (field (name "Manufacturer Part") "0402WGF0000TCE")
        (field (name "Manufacturer") "UNI-ROYAL(厚声)")
      )
      (libsource (lib "easyedapro") (part "0402WGF0000TCE"))
    )
    (comp (ref "R39")
      (value "0Ω")
      (footprint "easyedapro:R0402")
      (description "电阻类型:厚膜电阻;阻值:0Ω;精度:±1%;功率:62.5mW;")
      (fields
        (field (name "Manufacturer Part") "0402WGF0000TCE")
        (field (name "Manufacturer") "UNI-ROYAL(厚声)")
      )
      (libsource (lib "easyedapro") (part "0402WGF0000TCE"))
    )
    (comp (ref "R40")
      (value "10kΩ")
      (footprint "easyedapro:R0402")
      (description "电阻类型:厚膜电阻;阻值:10kΩ;精度:±1%;功率:62.5mW;温度系数:±100ppm/°C;")
      (fields
        (field (name "Manufacturer Part") "0402WGF1002TCE")
        (field (name "Manufacturer") "UNI-ROYAL(厚声)")
      )
      (libsource (lib "easyedapro") (part "0402WGF1002TCE"))
    )
    (comp (ref "R41")
      (value "0Ω")
      (footprint "easyedapro:R0402")
      (description "电阻类型:厚膜电阻;阻值:0Ω;精度:±1%;功率:62.5mW;")
      (fields
        (field (name "Manufacturer Part") "0402WGF0000TCE")
        (field (name "Manufacturer") "UNI-ROYAL(厚声)")
      )
      (libsource (lib "easyedapro") (part "0402WGF0000TCE"))
    )
    (comp (ref "R42")
      (value "100kΩ")
      (footprint "easyedapro:R0402")
      (description "电阻类型:厚膜电阻;阻值:100kΩ;精度:±1%;功率:62.5mW;")
      (fields
        (field (name "Manufacturer Part") "0402WGF1003TCE")
        (field (name "Manufacturer") "UNI-ROYAL(厚声)")
      )
      (libsource (lib "easyedapro") (part "0402WGF1003TCE"))
    )
    (comp (ref "R43")
      (value "100kΩ")
      (footprint "easyedapro:R0402")
      (description "电阻类型:厚膜电阻;阻值:100kΩ;精度:±1%;功率:62.5mW;")
      (fields
        (field (name "Manufacturer Part") "0402WGF1003TCE")
        (field (name "Manufacturer") "UNI-ROYAL(厚声)")
      )
      (libsource (lib "easyedapro") (part "0402WGF1003TCE"))
    )
    (comp (ref "R44")
      (value "0Ω")
      (footprint "easyedapro:R0402")
      (description "电阻类型:厚膜电阻;阻值:0Ω;精度:±1%;功率:62.5mW;")
      (fields
        (field (name "Manufacturer Part") "0402WGF0000TCE")
        (field (name "Manufacturer") "UNI-ROYAL(厚声)")
      )
      (libsource (lib "easyedapro") (part "0402WGF0000TCE"))
    )
    (comp (ref "R45")
      (value "0Ω")
      (footprint "easyedapro:R0402")
      (description "电阻类型:厚膜电阻;阻值:0Ω;精度:±1%;功率:62.5mW;")
      (fields
        (field (name "Manufacturer Part") "0402WGF0000TCE")
        (field (name "Manufacturer") "UNI-ROYAL(厚声)")
      )
      (libsource (lib "easyedapro") (part "0402WGF0000TCE"))
    )
    (comp (ref "R46")
      (value "0Ω")
      (footprint "easyedapro:R0402")
      (description "电阻类型:厚膜电阻;阻值:0Ω;精度:±1%;功率:62.5mW;")
      (fields
        (field (name "Manufacturer Part") "0402WGF0000TCE")
        (field (name "Manufacturer") "UNI-ROYAL(厚声)")
      )
      (libsource (lib "easyedapro") (part "0402WGF0000TCE"))
    )
    (comp (ref "R47")
      (value "0Ω")
      (footprint "easyedapro:R0402")
      (description "电阻类型:厚膜电阻;阻值:0Ω;精度:±1%;功率:62.5mW;")
      (fields
        (field (name "Manufacturer Part") "0402WGF0000TCE")
        (field (name "Manufacturer") "UNI-ROYAL(厚声)")
      )
      (libsource (lib "easyedapro") (part "0402WGF0000TCE"))
    )
    (comp (ref "R48")
      (value "0Ω")
      (footprint "easyedapro:R0402")
      (description "电阻类型:厚膜电阻;阻值:0Ω;精度:±1%;功率:62.5mW;")
      (fields
        (field (name "Manufacturer Part") "0402WGF0000TCE")
        (field (name "Manufacturer") "UNI-ROYAL(厚声)")
      )
      (libsource (lib "easyedapro") (part "0402WGF0000TCE"))
    )
    (comp (ref "R49")
      (value "0Ω")
      (footprint "easyedapro:R0402")
      (description "电阻类型:厚膜电阻;阻值:0Ω;精度:±1%;功率:62.5mW;")
      (fields
        (field (name "Manufacturer Part") "0402WGF0000TCE")
        (field (name "Manufacturer") "UNI-ROYAL(厚声)")
      )
      (libsource (lib "easyedapro") (part "0402WGF0000TCE"))
    )
    (comp (ref "R50")
      (value "0Ω")
      (footprint "easyedapro:R0402")
      (description "电阻类型:厚膜电阻;阻值:0Ω;精度:±1%;功率:62.5mW;")
      (fields
        (field (name "Manufacturer Part") "0402WGF0000TCE")
        (field (name "Manufacturer") "UNI-ROYAL(厚声)")
      )
      (libsource (lib "easyedapro") (part "0402WGF0000TCE"))
    )
    (comp (ref "R51")
      (value "0Ω")
      (footprint "easyedapro:R0402")
      (description "电阻类型:厚膜电阻;阻值:0Ω;精度:±1%;功率:62.5mW;")
      (fields
        (field (name "Manufacturer Part") "0402WGF0000TCE")
        (field (name "Manufacturer") "UNI-ROYAL(厚声)")
      )
      (libsource (lib "easyedapro") (part "0402WGF0000TCE"))
    )
    (comp (ref "R52")
      (value "0Ω")
      (footprint "easyedapro:R0402")
      (description "电阻类型:厚膜电阻;阻值:0Ω;精度:±1%;功率:62.5mW;")
      (fields
        (field (name "Manufacturer Part") "0402WGF0000TCE")
        (field (name "Manufacturer") "UNI-ROYAL(厚声)")
      )
      (libsource (lib "easyedapro") (part "0402WGF0000TCE"))
    )
    (comp (ref "U9")
      (value "ES8311")
      (footprint "easyedapro:WQFN-20_L3.0-W3.0-P0.40-BL-EP1.7")
      (fields (field (name "Manufacturer") "Everest-semi(顺芯)"))
      (libsource (lib "easyedapro") (part "ES8311"))
    )
    (comp (ref "U10")
      (value "ES7210")
      (footprint "easyedapro:QFN-32_L4.0-W4.0-P0.40-BL-EP2.7")
      (description "供电电压:-；-；-；-；-;")
      (fields (field (name "Manufacturer") "Everest-semi(顺芯)"))
      (libsource (lib "easyedapro") (part "ES7210"))
    )
    (comp (ref "U11")
      (value "NS4150B")
      (footprint "easyedapro:MSOP-8_L3.0-W3.0-P0.65-LS5.0-BL")
      (description "功放类型:Class D;输出功率:3Wx1@4Ω;")
      (fields (field (name "Manufacturer") "Nsiway(纳芯威)"))
      (libsource (lib "easyedapro") (part "NS4150"))
    )
  )
  (nets
    (net (code "1") (name "2V8") (class "Default")
      (node (ref "C27") (pin "1") (pinfunction "1_1") (pintype "input"))
      (node (ref "C33") (pin "2") (pinfunction "2_2") (pintype "input"))
      (node (ref "J6") (pin "11") (pinfunction "11_11") (pintype "unspecified"))
      (node (ref "U7") (pin "5") (pinfunction "VOUT_5") (pintype "unspecified"))
    )
    (net (code "2") (name "3V3") (class "Default")
      (node (ref "C12") (pin "1") (pinfunction "1_1") (pintype "input"))
      (node (ref "C13") (pin "2") (pinfunction "2_2") (pintype "input"))
      (node (ref "C14") (pin "2") (pinfunction "2_2") (pintype "input"))
      (node (ref "C15") (pin "2") (pinfunction "2_2") (pintype "input"))
      (node (ref "C16") (pin "2") (pinfunction "2_2") (pintype "input"))
      (node (ref "C17") (pin "1") (pinfunction "1_1") (pintype "input"))
      (node (ref "C18") (pin "2") (pinfunction "2_2") (pintype "input"))
      (node (ref "C19") (pin "2") (pinfunction "2_2") (pintype "input"))
      (node (ref "C25") (pin "1") (pinfunction "1_1") (pintype "input"))
      (node (ref "C26") (pin "1") (pinfunction "1_1") (pintype "input"))
      (node (ref "C28") (pin "2") (pinfunction "2_2") (pintype "input"))
      (node (ref "C29") (pin "1") (pinfunction "1_1") (pintype "input"))
      (node (ref "C30") (pin "2") (pinfunction "2_2") (pintype "input"))
      (node (ref "C5") (pin "1") (pinfunction "1_1") (pintype "input"))
      (node (ref "C6") (pin "1") (pinfunction "1_1") (pintype "input"))
      (node (ref "C8") (pin "3") (pinfunction "OUT_3") (pintype "input"))
      (node (ref "C9") (pin "3") (pinfunction "OUT_3") (pintype "input"))
      (node (ref "J3") (pin "4") (pinfunction "VDD_4") (pintype "unspecified"))
      (node (ref "J4") (pin "7") (pinfunction "VDD_7") (pintype "input"))
      (node (ref "J5") (pin "1") (pinfunction "VDD_1") (pintype "input"))
      (node (ref "L3") (pin "1") (pinfunction "1_1") (pintype "unspecified"))
      (node (ref "R1") (pin "1") (pinfunction "1_1") (pintype "input"))
      (node (ref "R10") (pin "2") (pinfunction "2_2") (pintype "input"))
      (node (ref "R16") (pin "2") (pinfunction "2_2") (pintype "input"))
      (node (ref "R2") (pin "1") (pinfunction "1_1") (pintype "input"))
      (node (ref "R20") (pin "1") (pinfunction "1_1") (pintype "input"))
      (node (ref "R21") (pin "2") (pinfunction "2_2") (pintype "input"))
      (node (ref "R22") (pin "2") (pinfunction "2_2") (pintype "input"))
      (node (ref "R25") (pin "2") (pinfunction "2_2") (pintype "input"))
      (node (ref "R4") (pin "1") (pinfunction "1_1") (pintype "input"))
      (node (ref "R5") (pin "1") (pinfunction "1_1") (pintype "input"))
      (node (ref "R6") (pin "1") (pinfunction "1_1") (pintype "input"))
      (node (ref "R7") (pin "2") (pinfunction "2_2") (pintype "input"))
      (node (ref "R8") (pin "2") (pinfunction "2_2") (pintype "input"))
      (node (ref "R9") (pin "2") (pinfunction "2_2") (pintype "input"))
      (node (ref "U1") (pin "2") (pinfunction "3V3_2") (pintype "unspecified"))
      (node (ref "U2") (pin "16") (pinfunction "VDD_16") (pintype "unspecified"))
      (node (ref "U3") (pin "12") (pinfunction "CS_12") (pintype "unspecified"))
      (node (ref "U3") (pin "5") (pinfunction "VDDIO_5") (pintype "unspecified"))
      (node (ref "U3") (pin "8") (pinfunction "VDD_8") (pintype "unspecified"))
      (node (ref "U4") (pin "10") (pinfunction "V3_10") (pintype "unspecified"))
      (node (ref "U4") (pin "7") (pinfunction "VCC_7") (pintype "unspecified"))
      (node (ref "U5") (pin "19") (pinfunction "V5_19") (pintype "unspecified"))
      (node (ref "U5") (pin "20") (pinfunction "VDD33_20") (pintype "unspecified"))
      (node (ref "U7") (pin "1") (pinfunction "VIN_1") (pintype "unspecified"))
      (node (ref "U7") (pin "3") (pinfunction "CE_3") (pintype "unspecified"))
    )
    (net (code "3") (name "ADC_3V3") (class "Default")
      (node (ref "C56") (pin "2") (pinfunction "2_2") (pintype "input"))
      (node (ref "C57") (pin "2") (pinfunction "2_2") (pintype "input"))
      (node (ref "R26") (pin "2") (pinfunction "2_2") (pintype "input"))
      (node (ref "R30") (pin "2") (pinfunction "2_2") (pintype "input"))
      (node (ref "R33") (pin "2") (pinfunction "2_2") (pintype "input"))
      (node (ref "U10") (pin "6") (pinfunction "VDDP_6") (pintype "input"))
      (node (ref "U10") (pin "7") (pinfunction "VDDD_7") (pintype "input"))
    )
    (net (code "4") (name "ADC_MIC1N") (class "Default")
      (node (ref "C66") (pin "1") (pinfunction "1_1") (pintype "input"))
      (node (ref "R50") (pin "1") (pinfunction "1_1") (pintype "input"))
    )
    (net (code "5") (name "ADC_MIC1P") (class "Default")
      (node (ref "C65") (pin "1") (pinfunction "1_1") (pintype "input"))
      (node (ref "R49") (pin "1") (pinfunction "1_1") (pintype "input"))
    )
    (net (code "6") (name "ADC_MIC2N") (class "Default")
      (node (ref "C58") (pin "1") (pinfunction "1_1") (pintype "input"))
      (node (ref "R46") (pin "1") (pinfunction "1_1") (pintype "input"))
    )
    (net (code "7") (name "ADC_MIC2P") (class "Default")
      (node (ref "C61") (pin "1") (pinfunction "1_1") (pintype "input"))
      (node (ref "R45") (pin "1") (pinfunction "1_1") (pintype "input"))
    )
    (net (code "8") (name "ADC_MIC3N") (class "Default")
      (node (ref "C38") (pin "1") (pinfunction "1_1") (pintype "input"))
      (node (ref "R35") (pin "2") (pinfunction "2_2") (pintype "input"))
    )
    (net (code "9") (name "ADC_MIC3P") (class "Default")
      (node (ref "C36") (pin "1") (pinfunction "1_1") (pintype "input"))
      (node (ref "R34") (pin "2") (pinfunction "2_2") (pintype "input"))
    )
    (net (code "10") (name "ADC_MICBIAS12") (class "Default")
      (node (ref "C43") (pin "1") (pinfunction "1_1") (pintype "input"))
      (node (ref "R47") (pin "2") (pinfunction "2_2") (pintype "input"))
      (node (ref "R51") (pin "2") (pinfunction "2_2") (pintype "input"))
      (node (ref "U10") (pin "24") (pinfunction "MICBIAS12_24") (pintype "input"))
    )
    (net (code "11") (name "AU_3V3") (class "Default")
      (node (ref "C20") (pin "2") (pinfunction "2_2") (pintype "input"))
      (node (ref "C21") (pin "1") (pinfunction "1_1") (pintype "input"))
      (node (ref "C22") (pin "2") (pinfunction "2_2") (pintype "input"))
      (node (ref "C55") (pin "2") (pinfunction "2_2") (pintype "input"))
      (node (ref "L2") (pin "1") (pinfunction "1_1") (pintype "unspecified"))
      (node (ref "R17") (pin "2") (pinfunction "2_2") (pintype "input"))
      (node (ref "R28") (pin "1") (pinfunction "1_1") (pintype "input"))
      (node (ref "R33") (pin "1") (pinfunction "1_1") (pintype "input"))
    )
    (net (code "12") (name "AU_GND") (class "Default")
      (node (ref "C34") (pin "2") (pinfunction "2_2") (pintype "input"))
      (node (ref "C35") (pin "2") (pinfunction "2_2") (pintype "input"))
      (node (ref "C37") (pin "2") (pinfunction "2_2") (pintype "input"))
      (node (ref "C39") (pin "2") (pinfunction "2_2") (pintype "input"))
      (node (ref "C40") (pin "2") (pinfunction "2_2") (pintype "input"))
      (node (ref "C41") (pin "2") (pinfunction "2_2") (pintype "input"))
      (node (ref "C42") (pin "1") (pinfunction "1_1") (pintype "input"))
      (node (ref "C43") (pin "2") (pinfunction "2_2") (pintype "input"))
      (node (ref "C44") (pin "1") (pinfunction "1_1") (pintype "input"))
      (node (ref "C45") (pin "1") (pinfunction "1_1") (pintype "input"))
      (node (ref "C48") (pin "2") (pinfunction "2_2") (pintype "input"))
      (node (ref "C49") (pin "2") (pinfunction "2_2") (pintype "input"))
      (node (ref "C50") (pin "1") (pinfunction "1_1") (pintype "input"))
      (node (ref "C51") (pin "1") (pinfunction "1_1") (pintype "input"))
      (node (ref "C52") (pin "1") (pinfunction "1_1") (pintype "input"))
      (node (ref "C53") (pin "1") (pinfunction "1_1") (pintype "input"))
      (node (ref "C54") (pin "1") (pinfunction "1_1") (pintype "input"))
      (node (ref "C55") (pin "1") (pinfunction "1_1") (pintype "input"))
      (node (ref "C56") (pin "1") (pinfunction "1_1") (pintype "input"))
      (node (ref "C57") (pin "1") (pinfunction "1_1") (pintype "input"))
      (node (ref "C59") (pin "2") (pinfunction "2_2") (pintype "input"))
      (node (ref "C60") (pin "2") (pinfunction "2_2") (pintype "input"))
      (node (ref "C62") (pin "1") (pinfunction "1_1") (pintype "input"))
      (node (ref "C63") (pin "1") (pinfunction "1_1") (pintype "input"))
      (node (ref "C64") (pin "1") (pinfunction "1_1") (pintype "input"))
      (node (ref "C67") (pin "1") (pinfunction "1_1") (pintype "input"))
      (node (ref "C68") (pin "1") (pinfunction "1_1") (pintype "input"))
      (node (ref "C69") (pin "1") (pinfunction "1_1") (pintype "input"))
      (node (ref "C70") (pin "1") (pinfunction "1_1") (pintype "input"))
      (node (ref "C71") (pin "1") (pinfunction "1_1") (pintype "input"))
      (node (ref "C74") (pin "1") (pinfunction "1_1") (pintype "input"))
      (node (ref "C75") (pin "2") (pinfunction "2_2") (pintype "unspecified"))
      (node (ref "C76") (pin "2") (pinfunction "2_2") (pintype "unspecified"))
      (node (ref "C77") (pin "1") (pinfunction "1_1") (pintype "input"))
      (node (ref "C78") (pin "1") (pinfunction "1_1") (pintype "input"))
      (node (ref "C79") (pin "1") (pinfunction "1_1") (pintype "input"))
      (node (ref "C80") (pin "2") (pinfunction "2_2") (pintype "input"))
      (node (ref "C81") (pin "1") (pinfunction "1_1") (pintype "input"))
      (node (ref "C82") (pin "1") (pinfunction "1_1") (pintype "input"))
      (node (ref "C83") (pin "2") (pinfunction "2_2") (pintype "input"))
      (node (ref "C84") (pin "1") (pinfunction "1_1") (pintype "input"))
      (node (ref "C85") (pin "1") (pinfunction "1_1") (pintype "input"))
      (node (ref "R27") (pin "2") (pinfunction "2_2") (pintype "input"))
      (node (ref "R38") (pin "1") (pinfunction "1_1") (pintype "input"))
      (node (ref "R40") (pin "2") (pinfunction "2_2") (pintype "input"))
      (node (ref "R48") (pin "1") (pinfunction "1_1") (pintype "input"))
      (node (ref "R52") (pin "1") (pinfunction "1_1") (pintype "input"))
      (node (ref "U10") (pin "21") (pinfunction "GNDA_21") (pintype "input"))
      (node (ref "U10") (pin "33") (pinfunction "EP_33") (pintype "input"))
      (node (ref "U10") (pin "8") (pinfunction "GNDD_8") (pintype "input"))
      (node (ref "U11") (pin "7") (pinfunction "GND_7") (pintype "input"))
      (node (ref "U9") (pin "10") (pinfunction "AGND_10") (pintype "input"))
      (node (ref "U9") (pin "20") (pinfunction "CE_20") (pintype "input"))
      (node (ref "U9") (pin "21") (pinfunction "EP_21") (pintype "input"))
      (node (ref "U9") (pin "5") (pinfunction "DGND_5") (pintype "input"))
    )
    (net (code "13") (name "CH340_D+") (class "Default")
      (node (ref "U4") (pin "1") (pinfunction "UD+_1") (pintype "unspecified"))
      (node (ref "U5") (pin "6") (pinfunction "DP4_6") (pintype "unspecified"))
    )
    (net (code "14") (name "CH340_D-") (class "Default")
      (node (ref "U4") (pin "2") (pinfunction "UD-_2") (pintype "unspecified"))
      (node (ref "U5") (pin "5") (pinfunction "DM4_5") (pintype "unspecified"))
    )
    (net (code "15") (name "CODEC_3V3") (class "Default")
      (node (ref "C50") (pin "2") (pinfunction "2_2") (pintype "input"))
      (node (ref "C51") (pin "2") (pinfunction "2_2") (pintype "input"))
      (node (ref "R28") (pin "2") (pinfunction "2_2") (pintype "input"))
      (node (ref "R32") (pin "1") (pinfunction "1_1") (pintype "input"))
      (node (ref "U9") (pin "3") (pinfunction "PVDD_3") (pintype "input"))
      (node (ref "U9") (pin "4") (pinfunction "DVDD_4") (pintype "input"))
    )
    (net (code "16") (name "DTR") (class "Default")
      (node (ref "Q1") (pin "4") (pinfunction "E_4") (pintype "unspecified"))
      (node (ref "R13") (pin "2") (pinfunction "2_2") (pintype "input"))
      (node (ref "U4") (pin "4") (pinfunction "DTR#_4") (pintype "unspecified"))
    )
    (net (code "17") (name "DVP_PWDN") (class "Default")
      (node (ref "J6") (pin "8") (pinfunction "8_8") (pintype "unspecified"))
      (node (ref "R25") (pin "1") (pinfunction "1_1") (pintype "input"))
      (node (ref "U2") (pin "9") (pinfunction "IO2_9") (pintype "bidirectional"))
    )
    (net (code "18") (name "GND") (class "Default")
      (node (ref "C1") (pin "2") (pinfunction "GND_2") (pintype "input"))
      (node (ref "C10") (pin "2") (pinfunction "2_2") (pintype "input"))
      (node (ref "C11") (pin "2") (pinfunction "2_2") (pintype "input"))
      (node (ref "C12") (pin "2") (pinfunction "2_2") (pintype "input"))
      (node (ref "C13") (pin "1") (pinfunction "1_1") (pintype "input"))
      (node (ref "C14") (pin "1") (pinfunction "1_1") (pintype "input"))
      (node (ref "C15") (pin "1") (pinfunction "1_1") (pintype "input"))
      (node (ref "C16") (pin "1") (pinfunction "1_1") (pintype "input"))
      (node (ref "C17") (pin "2") (pinfunction "2_2") (pintype "input"))
      (node (ref "C18") (pin "1") (pinfunction "1_1") (pintype "input"))
      (node (ref "C19") (pin "1") (pinfunction "1_1") (pintype "input"))
      (node (ref "C2") (pin "2") (pinfunction "GND_2") (pintype "input"))
      (node (ref "C20") (pin "1") (pinfunction "1_1") (pintype "input"))
      (node (ref "C21") (pin "2") (pinfunction "2_2") (pintype "input"))
      (node (ref "C23") (pin "2") (pinfunction "2_2") (pintype "input"))
      (node (ref "C24") (pin "1") (pinfunction "1_1") (pintype "unspecified"))
      (node (ref "C25") (pin "2") (pinfunction "2_2") (pintype "input"))
      (node (ref "C26") (pin "2") (pinfunction "2_2") (pintype "input"))
      (node (ref "C27") (pin "2") (pinfunction "2_2") (pintype "input"))
      (node (ref "C28") (pin "1") (pinfunction "1_1") (pintype "input"))
      (node (ref "C29") (pin "2") (pinfunction "2_2") (pintype "input"))
      (node (ref "C3") (pin "2") (pinfunction "2_2") (pintype "input"))
      (node (ref "C31") (pin "2") (pinfunction "2_2") (pintype "input"))
      (node (ref "C32") (pin "1") (pinfunction "1_1") (pintype "unspecified"))
      (node (ref "C33") (pin "1") (pinfunction "1_1") (pintype "input"))
      (node (ref "C4") (pin "2") (pinfunction "2_2") (pintype "input"))
      (node (ref "C5") (pin "2") (pinfunction "2_2") (pintype "input"))
      (node (ref "C6") (pin "2") (pinfunction "2_2") (pintype "input"))
      (node (ref "C7") (pin "2") (pinfunction "2_2") (pintype "input"))
      (node (ref "C8") (pin "2") (pinfunction "GND_2") (pintype "input"))
      (node (ref "C9") (pin "2") (pinfunction "GND_2") (pintype "input"))
      (node (ref "D1") (pin "2") (pinfunction "2_2") (pintype "input"))
      (node (ref "D10") (pin "2") (pinfunction "2_2") (pintype "input"))
      (node (ref "D11") (pin "1") (pinfunction "1_1") (pintype "input"))
      (node (ref "D12") (pin "1") (pinfunction "1_1") (pintype "input"))
      (node (ref "D13") (pin "1") (pinfunction "1_1") (pintype "input"))
      (node (ref "D2") (pin "2") (pinfunction "2_2") (pintype "input"))
      (node (ref "D3") (pin "2") (pinfunction "2_2") (pintype "input"))
      (node (ref "D4") (pin "2") (pinfunction "2_2") (pintype "input"))
      (node (ref "D5") (pin "2") (pinfunction "2_2") (pintype "input"))
      (node (ref "D6") (pin "2") (pinfunction "2_2") (pintype "input"))
      (node (ref "D7") (pin "2") (pinfunction "2_2") (pintype "input"))
      (node (ref "D8") (pin "2") (pinfunction "2_2") (pintype "input"))
      (node (ref "D9") (pin "2") (pinfunction "2_2") (pintype "input"))
      (node (ref "J1") (pin "3") (pinfunction "3_3") (pintype "unspecified"))
      (node (ref "J1") (pin "6") (pinfunction "6_6") (pintype "unspecified"))
      (node (ref "J1") (pin "7") (pinfunction "7_7") (pintype "unspecified"))
      (node (ref "J2") (pin "3") (pinfunction "3_3") (pintype "unspecified"))
      (node (ref "J2") (pin "6") (pinfunction "6_6") (pintype "unspecified"))
      (node (ref "J2") (pin "7") (pinfunction "7_7") (pintype "unspecified"))
      (node (ref "J3") (pin "10") (pinfunction "10_10") (pintype "unspecified"))
      (node (ref "J3") (pin "11") (pinfunction "11_11") (pintype "unspecified"))
      (node (ref "J3") (pin "12") (pinfunction "12_12") (pintype "unspecified"))
      (node (ref "J3") (pin "13") (pinfunction "13_13") (pintype "unspecified"))
      (node (ref "J3") (pin "6") (pinfunction "VSS_6") (pintype "unspecified"))
      (node (ref "J4") (pin "10") (pinfunction "BL_K_10") (pintype "input"))
      (node (ref "J4") (pin "11") (pinfunction "11_11") (pintype "input"))
      (node (ref "J4") (pin "12") (pinfunction "12_12") (pintype "input"))
      (node (ref "J4") (pin "6") (pinfunction "GND_6") (pintype "input"))
      (node (ref "J4") (pin "8") (pinfunction "GND_8") (pintype "input"))
      (node (ref "J5") (pin "6") (pinfunction "GND_6") (pintype "input"))
      (node (ref "J5") (pin "7") (pinfunction "7_7") (pintype "input"))
      (node (ref "J5") (pin "8") (pinfunction "8_8") (pintype "input"))
      (node (ref "J6") (pin "15") (pinfunction "15_15") (pintype "unspecified"))
      (node (ref "J6") (pin "2") (pinfunction "2_2") (pintype "unspecified"))
      (node (ref "J7") (pin "3") (pinfunction "3_3") (pintype "input"))
      (node (ref "J7") (pin "4") (pinfunction "4_4") (pintype "input"))
      (node (ref "R11") (pin "1") (pinfunction "1_1") (pintype "input"))
      (node (ref "R12") (pin "2") (pinfunction "2_2") (pintype "input"))
      (node (ref "R18") (pin "1") (pinfunction "1_1") (pintype "input"))
      (node (ref "R24") (pin "1") (pinfunction "1_1") (pintype "input"))
      (node (ref "R3") (pin "1") (pinfunction "1_1") (pintype "input"))
      (node (ref "R38") (pin "2") (pinfunction "2_2") (pintype "input"))
      (node (ref "SW1") (pin "1") (pinfunction "1_1") (pintype "unspecified"))
      (node (ref "SW1") (pin "3") (pinfunction "3_3") (pintype "unspecified"))
      (node (ref "SW1") (pin "4") (pinfunction "4_4") (pintype "unspecified"))
      (node (ref "SW2") (pin "2") (pinfunction "2_2") (pintype "unspecified"))
      (node (ref "SW2") (pin "3") (pinfunction "3_3") (pintype "unspecified"))
      (node (ref "SW2") (pin "4") (pinfunction "4_4") (pintype "unspecified"))
      (node (ref "U1") (pin "1") (pinfunction "GND_1") (pintype "unspecified"))
      (node (ref "U1") (pin "40") (pinfunction "GND_40") (pintype "unspecified"))
      (node (ref "U1") (pin "41") (pinfunction "GND_41") (pintype "unspecified"))
      (node (ref "U2") (pin "4") (pinfunction "A1_4") (pintype "unspecified"))
      (node (ref "U2") (pin "5") (pinfunction "A2_5") (pintype "unspecified"))
      (node (ref "U2") (pin "8") (pinfunction "VSS_8") (pintype "unspecified"))
      (node (ref "U3") (pin "2") (pinfunction "SDX_2") (pintype "unspecified"))
      (node (ref "U3") (pin "3") (pinfunction "SCX_3") (pintype "unspecified"))
      (node (ref "U3") (pin "6") (pinfunction "GND_6") (pintype "unspecified"))
      (node (ref "U3") (pin "7") (pinfunction "GND_7") (pintype "unspecified"))
      (node (ref "U4") (pin "11") (pinfunction "GND_11") (pintype "unspecified"))
      (node (ref "U4") (pin "3") (pinfunction "GND_3") (pintype "unspecified"))
      (node (ref "U5") (pin "25") (pinfunction "GND_25") (pintype "unspecified"))
      (node (ref "U6") (pin "2") (pinfunction "GND_2") (pintype "input"))
      (node (ref "U7") (pin "2") (pinfunction "VSS_2") (pintype "unspecified"))
      (node (ref "U8") (pin "2") (pinfunction "GND_2") (pintype "input"))
      (node (ref "USB1") (pin "A1B12") (pinfunction "GND_A1B12") (pintype "unspecified"))
      (node (ref "USB1") (pin "B1A12") (pinfunction "GND_B1A12") (pintype "unspecified"))
      (node (ref "USB1") (pin "EP") (pinfunction "EP_EP") (pintype "unspecified"))
      (node (ref "X1") (pin "2") (pinfunction "GND_2") (pintype "unspecified"))
      (node (ref "X1") (pin "4") (pinfunction "GND_4") (pintype "unspecified"))
    )
    (net (code "19") (name "IO0_BOOT") (class "Default")
      (node (ref "Q1") (pin "3") (pinfunction "C_3") (pintype "unspecified"))
      (node (ref "R2") (pin "2") (pinfunction "2_2") (pintype "input"))
      (node (ref "SW2") (pin "1") (pinfunction "1_1") (pintype "unspecified"))
      (node (ref "U1") (pin "27") (pinfunction "IO0_27") (pintype "unspecified"))
    )
    (net (code "20") (name "IO1_I2C_SDA") (class "Default")
      (node (ref "D2") (pin "1") (pinfunction "1_1") (pintype "input"))
      (node (ref "J1") (pin "2") (pinfunction "2_2") (pintype "unspecified"))
      (node (ref "J5") (pin "4") (pinfunction "SDA_4") (pintype "input"))
      (node (ref "J6") (pin "3") (pinfunction "3_3") (pintype "unspecified"))
      (node (ref "R4") (pin "2") (pinfunction "2_2") (pintype "input"))
      (node (ref "U1") (pin "39") (pinfunction "IO1_39") (pintype "unspecified"))
      (node (ref "U10") (pin "3") (pinfunction "CDATA_3") (pintype "input"))
      (node (ref "U2") (pin "2") (pinfunction "SDA_2") (pintype "bidirectional"))
      (node (ref "U3") (pin "14") (pinfunction "SDA_14") (pintype "unspecified"))
      (node (ref "U9") (pin "19") (pinfunction "CDATA_19") (pintype "input"))
    )
    (net (code "21") (name "IO2_I2C_SCL") (class "Default")
      (node (ref "D1") (pin "1") (pinfunction "1_1") (pintype "input"))
      (node (ref "J1") (pin "1") (pinfunction "1_1") (pintype "unspecified"))
      (node (ref "J5") (pin "3") (pinfunction "SCL_3") (pintype "input"))
      (node (ref "J6") (pin "5") (pinfunction "5_5") (pintype "unspecified"))
      (node (ref "R6") (pin "2") (pinfunction "2_2") (pintype "input"))
      (node (ref "U1") (pin "38") (pinfunction "IO2_38") (pintype "unspecified"))
      (node (ref "U10") (pin "4") (pinfunction "CCLK_4") (pintype "input"))
      (node (ref "U2") (pin "1") (pinfunction "SCL_1") (pintype "unspecified"))
      (node (ref "U3") (pin "13") (pinfunction "SCL_13") (pintype "unspecified"))
      (node (ref "U9") (pin "1") (pinfunction "CCLK_1") (pintype "input"))
    )
    (net (code "22") (name "IO3_DVP_VSYNC") (class "Default")
      (node (ref "J6") (pin "7") (pinfunction "7_7") (pintype "unspecified"))
      (node (ref "U1") (pin "15") (pinfunction "IO3_15") (pintype "unspecified"))
    )
    (net (code "23") (name "IO4_DVP_D6") (class "Default")
      (node (ref "J6") (pin "14") (pinfunction "14_14") (pintype "unspecified"))
      (node (ref "U1") (pin "4") (pinfunction "IO4_4") (pintype "unspecified"))
    )
    (net (code "24") (name "IO5_DVP_XCLK") (class "Default")
      (node (ref "J6") (pin "13") (pinfunction "13_13") (pintype "unspecified"))
      (node (ref "U1") (pin "5") (pinfunction "IO5_5") (pintype "unspecified"))
    )
    (net (code "25") (name "IO6_DVP_D5") (class "Default")
      (node (ref "J6") (pin "16") (pinfunction "16_16") (pintype "unspecified"))
      (node (ref "U1") (pin "6") (pinfunction "IO6_6") (pintype "unspecified"))
    )
    (net (code "26") (name "IO7_DVP_PCLK") (class "Default")
      (node (ref "J6") (pin "17") (pinfunction "17_17") (pintype "unspecified"))
      (node (ref "U1") (pin "7") (pinfunction "IO7_7") (pintype "unspecified"))
    )
    (net (code "27") (name "IO8_DVP_D2") (class "Default")
      (node (ref "J6") (pin "22") (pinfunction "22_22") (pintype "unspecified"))
      (node (ref "U1") (pin "12") (pinfunction "IO8_12") (pintype "unspecified"))
    )
    (net (code "28") (name "IO9_DVP_D7") (class "Default")
      (node (ref "J6") (pin "12") (pinfunction "12_12") (pintype "unspecified"))
      (node (ref "U1") (pin "17") (pinfunction "IO9_17") (pintype "unspecified"))
    )
    (net (code "29") (name "IO10") (class "Default")
      (node (ref "D4") (pin "1") (pinfunction "1_1") (pintype "input"))
      (node (ref "J2") (pin "2") (pinfunction "2_2") (pintype "unspecified"))
      (node (ref "U1") (pin "18") (pinfunction "IO10_18") (pintype "unspecified"))
    )
    (net (code "30") (name "IO11") (class "Default")
      (node (ref "D3") (pin "1") (pinfunction "1_1") (pintype "input"))
      (node (ref "J2") (pin "1") (pinfunction "1_1") (pintype "unspecified"))
      (node (ref "U1") (pin "19") (pinfunction "IO11_19") (pintype "unspecified"))
    )
    (net (code "31") (name "IO12_I2S_DI") (class "Default")
      (node (ref "R36") (pin "1") (pinfunction "1_1") (pintype "input"))
      (node (ref "R37") (pin "1") (pinfunction "1_1") (pintype "input"))
      (node (ref "U1") (pin "20") (pinfunction "IO12_20") (pintype "unspecified"))
    )
    (net (code "32") (name "IO13_I2S_WS") (class "Default")
      (node (ref "C64") (pin "2") (pinfunction "2_2") (pintype "input"))
      (node (ref "C69") (pin "2") (pinfunction "2_2") (pintype "input"))
      (node (ref "U1") (pin "21") (pinfunction "IO13_21") (pintype "unspecified"))
      (node (ref "U10") (pin "10") (pinfunction "LRCK_10") (pintype "input"))
      (node (ref "U9") (pin "8") (pinfunction "LRCK_8") (pintype "input"))
    )
    (net (code "33") (name "IO14_I2S_BCK") (class "Default")
      (node (ref "C63") (pin "2") (pinfunction "2_2") (pintype "input"))
      (node (ref "C68") (pin "2") (pinfunction "2_2") (pintype "input"))
      (node (ref "U1") (pin "22") (pinfunction "IO14_22") (pintype "unspecified"))
      (node (ref "U10") (pin "9") (pinfunction "SCLK_9") (pintype "input"))
      (node (ref "U9") (pin "6") (pinfunction "SCLK/DMIC_SCL_6") (pintype "input"))
    )
    (net (code "34") (name "IO15_DVP_D4") (class "Default")
      (node (ref "J6") (pin "18") (pinfunction "18_18") (pintype "unspecified"))
      (node (ref "U1") (pin "8") (pinfunction "IO15_8") (pintype "unspecified"))
    )
    (net (code "35") (name "IO16_DVP_D0") (class "Default")
      (node (ref "J6") (pin "19") (pinfunction "19_19") (pintype "unspecified"))
      (node (ref "U1") (pin "9") (pinfunction "IO16_9") (pintype "unspecified"))
    )
    (net (code "36") (name "IO17_DVP_D3") (class "Default")
      (node (ref "J6") (pin "20") (pinfunction "20_20") (pintype "unspecified"))
      (node (ref "U1") (pin "10") (pinfunction "IO17_10") (pintype "unspecified"))
    )
    (net (code "37") (name "IO18_DVP_D1") (class "Default")
      (node (ref "J6") (pin "21") (pinfunction "21_21") (pintype "unspecified"))
      (node (ref "U1") (pin "11") (pinfunction "IO18_11") (pintype "unspecified"))
    )
    (net (code "38") (name "IO19_USB_D-") (class "Default")
      (node (ref "U1") (pin "13") (pinfunction "IO19_13") (pintype "unspecified"))
      (node (ref "U5") (pin "7") (pinfunction "DM3_7") (pintype "unspecified"))
    )
    (net (code "39") (name "IO20_USB_D+") (class "Default")
      (node (ref "U1") (pin "14") (pinfunction "IO20_14") (pintype "unspecified"))
      (node (ref "U5") (pin "8") (pinfunction "DP3_8") (pintype "unspecified"))
    )
    (net (code "40") (name "IO21_SD_DAT0") (class "Default")
      (node (ref "D5") (pin "1") (pinfunction "1_1") (pintype "input"))
      (node (ref "J3") (pin "7") (pinfunction "DAT0_7") (pintype "unspecified"))
      (node (ref "R7") (pin "1") (pinfunction "1_1") (pintype "input"))
      (node (ref "U1") (pin "23") (pinfunction "IO21_23") (pintype "unspecified"))
    )
    (net (code "41") (name "IO38_I2S_MCK") (class "Default")
      (node (ref "C62") (pin "2") (pinfunction "2_2") (pintype "input"))
      (node (ref "C67") (pin "2") (pinfunction "2_2") (pintype "input"))
      (node (ref "U1") (pin "31") (pinfunction "IO38_31") (pintype "unspecified"))
      (node (ref "U10") (pin "5") (pinfunction "MCLK_5") (pintype "input"))
      (node (ref "U9") (pin "2") (pinfunction "MCLK_2") (pintype "input"))
    )
    (net (code "42") (name "IO39_LCD_DC") (class "Default")
      (node (ref "J4") (pin "1") (pinfunction "DC_1") (pintype "input"))
      (node (ref "U1") (pin "32") (pinfunction "IO39_32") (pintype "unspecified"))
    )
    (net (code "43") (name "IO40_LCD_MOSI") (class "Default")
      (node (ref "J4") (pin "2") (pinfunction "SDA_2") (pintype "input"))
      (node (ref "U1") (pin "33") (pinfunction "IO40_33") (pintype "unspecified"))
    )
    (net (code "44") (name "IO41_LCD_SCK") (class "Default")
      (node (ref "J4") (pin "5") (pinfunction "SCL_5") (pintype "input"))
      (node (ref "U1") (pin "34") (pinfunction "IO41_34") (pintype "unspecified"))
    )
    (net (code "45") (name "IO42_LCD_BL") (class "Default")
      (node (ref "R21") (pin "1") (pinfunction "1_1") (pintype "input"))
      (node (ref "R23") (pin "1") (pinfunction "1_1") (pintype "input"))
      (node (ref "U1") (pin "35") (pinfunction "IO42_35") (pintype "unspecified"))
    )
    (net (code "46") (name "IO45_I2S_DO") (class "Default")
      (node (ref "U1") (pin "26") (pinfunction "IO45_26") (pintype "unspecified"))
      (node (ref "U9") (pin "9") (pinfunction "DSDIN_9") (pintype "input"))
    )
    (net (code "47") (name "IO46_DVP_HREF") (class "Default")
      (node (ref "J6") (pin "9") (pinfunction "9_9") (pintype "unspecified"))
      (node (ref "R3") (pin "2") (pinfunction "2_2") (pintype "input"))
      (node (ref "U1") (pin "16") (pinfunction "IO46_16") (pintype "unspecified"))
    )
    (net (code "48") (name "IO47_SD_CLK") (class "Default")
      (node (ref "D6") (pin "1") (pinfunction "1_1") (pintype "input"))
      (node (ref "J3") (pin "5") (pinfunction "CLX_5") (pintype "unspecified"))
      (node (ref "R8") (pin "1") (pinfunction "1_1") (pintype "input"))
      (node (ref "U1") (pin "24") (pinfunction "IO47_24") (pintype "unspecified"))
    )
    (net (code "49") (name "IO48_SD_CMD") (class "Default")
      (node (ref "D7") (pin "1") (pinfunction "1_1") (pintype "input"))
      (node (ref "J3") (pin "3") (pinfunction "CMD_3") (pintype "unspecified"))
      (node (ref "R9") (pin "1") (pinfunction "1_1") (pintype "input"))
      (node (ref "U1") (pin "25") (pinfunction "IO48_25") (pintype "unspecified"))
    )
    (net (code "50") (name "LCD_CS") (class "Default")
      (node (ref "J4") (pin "3") (pinfunction "CS_3") (pintype "input"))
      (node (ref "R16") (pin "1") (pinfunction "1_1") (pintype "input"))
      (node (ref "U2") (pin "6") (pinfunction "IO0_6") (pintype "bidirectional"))
    )
    (net (code "51") (name "Net-(C1-IN)") (class "Default")
      (node (ref "C1") (pin "1") (pinfunction "IN_1") (pintype "input"))
      (node (ref "C3") (pin "1") (pinfunction "1_1") (pintype "input"))
      (node (ref "J1") (pin "5") (pinfunction "5_5") (pintype "unspecified"))
    )
    (net (code "52") (name "Net-(C2-IN)") (class "Default")
      (node (ref "C2") (pin "1") (pinfunction "IN_1") (pintype "input"))
      (node (ref "C4") (pin "1") (pinfunction "1_1") (pintype "input"))
      (node (ref "J2") (pin "5") (pinfunction "5_5") (pintype "unspecified"))
    )
    (net (code "53") (name "Net-(C8-IN)") (class "Default")
      (node (ref "C10") (pin "1") (pinfunction "1_1") (pintype "input"))
      (node (ref "C8") (pin "1") (pinfunction "IN_1") (pintype "input"))
      (node (ref "J1") (pin "4") (pinfunction "4_4") (pintype "unspecified"))
    )
    (net (code "54") (name "Net-(C9-IN)") (class "Default")
      (node (ref "C11") (pin "1") (pinfunction "1_1") (pintype "input"))
      (node (ref "C9") (pin "1") (pinfunction "IN_1") (pintype "input"))
      (node (ref "J2") (pin "4") (pinfunction "4_4") (pintype "unspecified"))
    )
    (net (code "55") (name "Net-(C46-Pad1)") (class "Default")
      (node (ref "C46") (pin "1") (pinfunction "1_1") (pintype "input"))
      (node (ref "R31") (pin "1") (pinfunction "1_1") (pintype "input"))
    )
    (net (code "56") (name "Net-(C47-Pad1)") (class "Default")
      (node (ref "C47") (pin "1") (pinfunction "1_1") (pintype "input"))
      (node (ref "R29") (pin "1") (pinfunction "1_1") (pintype "input"))
    )
    (net (code "57") (name "Net-(C70-Pad2)") (class "Default")
      (node (ref "C70") (pin "2") (pinfunction "2_2") (pintype "input"))
      (node (ref "J7") (pin "2") (pinfunction "2_2") (pintype "input"))
      (node (ref "R41") (pin "2") (pinfunction "2_2") (pintype "input"))
    )
    (net (code "58") (name "Net-(C71-Pad2)") (class "Default")
      (node (ref "C71") (pin "2") (pinfunction "2_2") (pintype "input"))
      (node (ref "J7") (pin "1") (pinfunction "1_1") (pintype "input"))
      (node (ref "R39") (pin "2") (pinfunction "2_2") (pintype "input"))
    )
    (net (code "59") (name "Net-(C72-Pad2)") (class "Default")
      (node (ref "C72") (pin "2") (pinfunction "2_2") (pintype "input"))
      (node (ref "R42") (pin "2") (pinfunction "2_2") (pintype "input"))
    )
    (net (code "60") (name "Net-(C73-Pad2)") (class "Default")
      (node (ref "C73") (pin "2") (pinfunction "2_2") (pintype "input"))
      (node (ref "R43") (pin "2") (pinfunction "2_2") (pintype "input"))
    )
    (net (code "61") (name "Net-(D12-Pad2)") (class "Default")
      (node (ref "D12") (pin "2") (pinfunction "2_2") (pintype "input"))
      (node (ref "F1") (pin "2") (pinfunction "2_2") (pintype "unspecified"))
      (node (ref "L1") (pin "2") (pinfunction "2_2") (pintype "input"))
    )
    (net (code "62") (name "Net-(J3-CD{slash}DAT3)") (class "Default")
      (node (ref "D8") (pin "1") (pinfunction "1_1") (pintype "input"))
      (node (ref "J3") (pin "2") (pinfunction "CD/DAT3_2") (pintype "unspecified"))
      (node (ref "R10") (pin "1") (pinfunction "1_1") (pintype "input"))
    )
    (net (code "63") (name "Net-(J3-DAT1)") (class "Default")
      (node (ref "D10") (pin "1") (pinfunction "1_1") (pintype "input"))
      (node (ref "J3") (pin "8") (pinfunction "DAT1_8") (pintype "unspecified"))
    )
    (net (code "64") (name "Net-(J3-DAT2)") (class "Default")
      (node (ref "D9") (pin "1") (pinfunction "1_1") (pintype "input"))
      (node (ref "J3") (pin "1") (pinfunction "DAT2_1") (pintype "unspecified"))
    )
    (net (code "65") (name "Net-(J4-BL_A)") (class "Default")
      (node (ref "J4") (pin "9") (pinfunction "BL_A_9") (pintype "input"))
      (node (ref "Q2") (pin "3") (pinfunction "D_3") (pintype "input"))
    )
    (net (code "66") (name "Net-(L1-Pad1)") (class "Default")
      (node (ref "L1") (pin "1") (pinfunction "1_1") (pintype "input"))
      (node (ref "USB1") (pin "A4B9") (pinfunction "VBUS_A4B9") (pintype "unspecified"))
      (node (ref "USB1") (pin "B4A9") (pinfunction "VBUS_B4A9") (pintype "unspecified"))
    )
    (net (code "67") (name "Net-(MIC1-GND-Pad2)") (class "Default")
      (node (ref "MIC1") (pin "2") (pinfunction "GND_2") (pintype "input"))
      (node (ref "MIC1") (pin "3") (pinfunction "GND_3") (pintype "input"))
      (node (ref "R50") (pin "2") (pinfunction "2_2") (pintype "input"))
      (node (ref "R52") (pin "2") (pinfunction "2_2") (pintype "input"))
    )
    (net (code "68") (name "Net-(MIC1-OUT)") (class "Default")
      (node (ref "C85") (pin "2") (pinfunction "2_2") (pintype "input"))
      (node (ref "MIC1") (pin "1") (pinfunction "OUT_1") (pintype "input"))
      (node (ref "R49") (pin "2") (pinfunction "2_2") (pintype "input"))
    )
    (net (code "69") (name "Net-(MIC1-VDD)") (class "Default")
      (node (ref "C83") (pin "1") (pinfunction "1_1") (pintype "input"))
      (node (ref "C84") (pin "2") (pinfunction "2_2") (pintype "input"))
      (node (ref "MIC1") (pin "4") (pinfunction "VDD_4") (pintype "input"))
      (node (ref "R51") (pin "1") (pinfunction "1_1") (pintype "input"))
    )
    (net (code "70") (name "Net-(MIC2-GND-Pad2)") (class "Default")
      (node (ref "MIC2") (pin "2") (pinfunction "GND_2") (pintype "input"))
      (node (ref "MIC2") (pin "3") (pinfunction "GND_3") (pintype "input"))
      (node (ref "R46") (pin "2") (pinfunction "2_2") (pintype "input"))
      (node (ref "R48") (pin "2") (pinfunction "2_2") (pintype "input"))
    )
    (net (code "71") (name "Net-(MIC2-OUT)") (class "Default")
      (node (ref "C82") (pin "2") (pinfunction "2_2") (pintype "input"))
      (node (ref "MIC2") (pin "1") (pinfunction "OUT_1") (pintype "input"))
      (node (ref "R45") (pin "2") (pinfunction "2_2") (pintype "input"))
    )
    (net (code "72") (name "Net-(MIC2-VDD)") (class "Default")
      (node (ref "C80") (pin "1") (pinfunction "1_1") (pintype "input"))
      (node (ref "C81") (pin "2") (pinfunction "2_2") (pintype "input"))
      (node (ref "MIC2") (pin "4") (pinfunction "VDD_4") (pintype "input"))
      (node (ref "R47") (pin "1") (pinfunction "1_1") (pintype "input"))
    )
    (net (code "73") (name "Net-(Q1-B-Pad2)") (class "Default")
      (node (ref "Q1") (pin "2") (pinfunction "B_2") (pintype "unspecified"))
      (node (ref "R13") (pin "1") (pinfunction "1_1") (pintype "input"))
    )
    (net (code "74") (name "Net-(Q1-B-Pad5)") (class "Default")
      (node (ref "Q1") (pin "5") (pinfunction "B_5") (pintype "unspecified"))
      (node (ref "R14") (pin "1") (pinfunction "1_1") (pintype "input"))
    )
    (net (code "75") (name "Net-(Q2-G)") (class "Default")
      (node (ref "Q2") (pin "1") (pinfunction "G_1") (pintype "input"))
      (node (ref "R23") (pin "2") (pinfunction "2_2") (pintype "input"))
    )
    (net (code "76") (name "Net-(Q2-S)") (class "Default")
      (node (ref "Q2") (pin "2") (pinfunction "S_2") (pintype "input"))
      (node (ref "R20") (pin "2") (pinfunction "2_2") (pintype "input"))
    )
    (net (code "77") (name "Net-(U2-A0)") (class "Default")
      (node (ref "R5") (pin "2") (pinfunction "2_2") (pintype "input"))
      (node (ref "U2") (pin "3") (pinfunction "A0_3") (pintype "unspecified"))
    )
    (net (code "78") (name "Net-(U5-XI)") (class "Default")
      (node (ref "U5") (pin "4") (pinfunction "XI_4") (pintype "unspecified"))
      (node (ref "X1") (pin "1") (pinfunction "OSC1_1") (pintype "unspecified"))
    )
    (net (code "79") (name "Net-(U5-XO)") (class "Default")
      (node (ref "U5") (pin "3") (pinfunction "XO_3") (pintype "unspecified"))
      (node (ref "X1") (pin "3") (pinfunction "OSC2_3") (pintype "unspecified"))
    )
    (net (code "80") (name "Net-(U6-EN)") (class "Default")
      (node (ref "R15") (pin "1") (pinfunction "1_1") (pintype "input"))
      (node (ref "U6") (pin "1") (pinfunction "EN_1") (pintype "input"))
    )
    (net (code "81") (name "Net-(U6-FB)") (class "Default")
      (node (ref "C22") (pin "1") (pinfunction "1_1") (pintype "input"))
      (node (ref "R17") (pin "1") (pinfunction "1_1") (pintype "input"))
      (node (ref "R18") (pin "2") (pinfunction "2_2") (pintype "input"))
      (node (ref "U6") (pin "5") (pinfunction "FB_5") (pintype "input"))
    )
    (net (code "82") (name "Net-(U6-LX)") (class "Default")
      (node (ref "L2") (pin "2") (pinfunction "2_2") (pintype "unspecified"))
      (node (ref "U6") (pin "3") (pinfunction "LX_3") (pintype "input"))
    )
    (net (code "83") (name "Net-(U8-EN)") (class "Default")
      (node (ref "R19") (pin "1") (pinfunction "1_1") (pintype "input"))
      (node (ref "U8") (pin "1") (pinfunction "EN_1") (pintype "input"))
    )
    (net (code "84") (name "Net-(U8-FB)") (class "Default")
      (node (ref "C30") (pin "1") (pinfunction "1_1") (pintype "input"))
      (node (ref "R22") (pin "1") (pinfunction "1_1") (pintype "input"))
      (node (ref "R24") (pin "2") (pinfunction "2_2") (pintype "input"))
      (node (ref "U8") (pin "5") (pinfunction "FB_5") (pintype "input"))
    )
    (net (code "85") (name "Net-(U8-LX)") (class "Default")
      (node (ref "L3") (pin "2") (pinfunction "2_2") (pintype "unspecified"))
      (node (ref "U8") (pin "3") (pinfunction "LX_3") (pintype "input"))
    )
    (net (code "86") (name "Net-(U9-ADCVREF)") (class "Default")
      (node (ref "C44") (pin "2") (pinfunction "2_2") (pintype "input"))
      (node (ref "U9") (pin "15") (pinfunction "ADCVREF_15") (pintype "input"))
    )
    (net (code "87") (name "Net-(U9-AVDD)") (class "Default")
      (node (ref "C52") (pin "2") (pinfunction "2_2") (pintype "input"))
      (node (ref "R32") (pin "2") (pinfunction "2_2") (pintype "input"))
      (node (ref "U9") (pin "11") (pinfunction "AVDD_11") (pintype "input"))
    )
    (net (code "88") (name "Net-(U9-DACVREF)") (class "Default")
      (node (ref "C45") (pin "2") (pinfunction "2_2") (pintype "input"))
      (node (ref "U9") (pin "14") (pinfunction "DACVREF_14") (pintype "input"))
    )
    (net (code "89") (name "Net-(U9-OUTN)") (class "Default")
      (node (ref "C47") (pin "2") (pinfunction "2_2") (pintype "input"))
      (node (ref "C54") (pin "2") (pinfunction "2_2") (pintype "input"))
      (node (ref "U9") (pin "13") (pinfunction "OUTN_13") (pintype "input"))
    )
    (net (code "90") (name "Net-(U9-OUTP)") (class "Default")
      (node (ref "C46") (pin "2") (pinfunction "2_2") (pintype "input"))
      (node (ref "C53") (pin "2") (pinfunction "2_2") (pintype "input"))
      (node (ref "U9") (pin "12") (pinfunction "OUTP_12") (pintype "input"))
    )
    (net (code "91") (name "Net-(U9-VMID)") (class "Default")
      (node (ref "C42") (pin "2") (pinfunction "2_2") (pintype "input"))
      (node (ref "U9") (pin "16") (pinfunction "VMID_16") (pintype "input"))
    )
    (net (code "92") (name "Net-(U10-AD0)") (class "Default")
      (node (ref "R26") (pin "1") (pinfunction "1_1") (pintype "input"))
      (node (ref "U10") (pin "1") (pinfunction "AD0_1") (pintype "input"))
    )
    (net (code "93") (name "Net-(U10-AD1)") (class "Default")
      (node (ref "R27") (pin "1") (pinfunction "1_1") (pintype "input"))
      (node (ref "U10") (pin "2") (pinfunction "AD1_2") (pintype "input"))
    )
    (net (code "94") (name "Net-(U10-MIC1N)") (class "Default")
      (node (ref "C66") (pin "2") (pinfunction "2_2") (pintype "input"))
      (node (ref "U10") (pin "15") (pinfunction "MIC1N_15") (pintype "input"))
    )
    (net (code "95") (name "Net-(U10-MIC1P)") (class "Default")
      (node (ref "C65") (pin "2") (pinfunction "2_2") (pintype "input"))
      (node (ref "U10") (pin "16") (pinfunction "MIC1P_16") (pintype "input"))
    )
    (net (code "96") (name "Net-(U10-MIC2N)") (class "Default")
      (node (ref "C58") (pin "2") (pinfunction "2_2") (pintype "input"))
      (node (ref "U10") (pin "20") (pinfunction "MIC2N_20") (pintype "input"))
    )
    (net (code "97") (name "Net-(U10-MIC2P)") (class "Default")
      (node (ref "C61") (pin "2") (pinfunction "2_2") (pintype "input"))
      (node (ref "U10") (pin "19") (pinfunction "MIC2P_19") (pintype "input"))
    )
    (net (code "98") (name "Net-(U10-MIC3N)") (class "Default")
      (node (ref "C38") (pin "2") (pinfunction "2_2") (pintype "input"))
      (node (ref "U10") (pin "32") (pinfunction "MIC3N_32") (pintype "input"))
    )
    (net (code "99") (name "Net-(U10-MIC3P)") (class "Default")
      (node (ref "C36") (pin "2") (pinfunction "2_2") (pintype "input"))
      (node (ref "U10") (pin "31") (pinfunction "MIC3P_31") (pintype "input"))
    )
    (net (code "100") (name "Net-(U10-MIC4N)") (class "Default")
      (node (ref "C39") (pin "1") (pinfunction "1_1") (pintype "input"))
      (node (ref "U10") (pin "27") (pinfunction "MIC4N_27") (pintype "input"))
    )
    (net (code "101") (name "Net-(U10-MIC4P)") (class "Default")
      (node (ref "C37") (pin "1") (pinfunction "1_1") (pintype "input"))
      (node (ref "U10") (pin "28") (pinfunction "MIC4P_28") (pintype "input"))
    )
    (net (code "102") (name "Net-(U10-MICBIAS34)") (class "Default")
      (node (ref "C40") (pin "1") (pinfunction "1_1") (pintype "input"))
      (node (ref "U10") (pin "26") (pinfunction "MICBIAS34_26") (pintype "input"))
    )
    (net (code "103") (name "Net-(U10-REFP12)") (class "Default")
      (node (ref "C59") (pin "1") (pinfunction "1_1") (pintype "input"))
      (node (ref "U10") (pin "17") (pinfunction "REFP12_17") (pintype "input"))
    )
    (net (code "104") (name "Net-(U10-REFP34)") (class "Default")
      (node (ref "C35") (pin "1") (pinfunction "1_1") (pintype "input"))
      (node (ref "U10") (pin "29") (pinfunction "REFP34_29") (pintype "input"))
    )
    (net (code "105") (name "Net-(U10-REFQ12)") (class "Default")
      (node (ref "C60") (pin "1") (pinfunction "1_1") (pintype "input"))
      (node (ref "U10") (pin "18") (pinfunction "REFQ12_18") (pintype "input"))
    )
    (net (code "106") (name "Net-(U10-REFQ34)") (class "Default")
      (node (ref "C34") (pin "1") (pinfunction "1_1") (pintype "input"))
      (node (ref "U10") (pin "30") (pinfunction "REFQ34_30") (pintype "input"))
    )
    (net (code "107") (name "Net-(U10-REFQM)") (class "Default")
      (node (ref "C41") (pin "1") (pinfunction "1_1") (pintype "input"))
      (node (ref "U10") (pin "25") (pinfunction "REFQM_25") (pintype "input"))
    )
    (net (code "108") (name "Net-(U10-SDOUT1{slash}TDMOUT)") (class "Default")
      (node (ref "R36") (pin "2") (pinfunction "2_2") (pintype "input"))
      (node (ref "U10") (pin "11") (pinfunction "SDOUT1/TDMOUT_11") (pintype "input"))
    )
    (net (code "109") (name "Net-(U10-SDOUT2{slash}TDMIN)") (class "Default")
      (node (ref "R37") (pin "2") (pinfunction "2_2") (pintype "input"))
      (node (ref "U10") (pin "12") (pinfunction "SDOUT2/TDMIN_12") (pintype "input"))
    )
    (net (code "110") (name "Net-(U10-VDDA)") (class "Default")
      (node (ref "C48") (pin "1") (pinfunction "1_1") (pintype "input"))
      (node (ref "C49") (pin "1") (pinfunction "1_1") (pintype "input"))
      (node (ref "R30") (pin "1") (pinfunction "1_1") (pintype "input"))
      (node (ref "U10") (pin "22") (pinfunction "VDDA_22") (pintype "input"))
      (node (ref "U10") (pin "23") (pinfunction "VDDM_23") (pintype "input"))
    )
    (net (code "111") (name "Net-(U11-Bypass)") (class "Default")
      (node (ref "C79") (pin "2") (pinfunction "2_2") (pintype "input"))
      (node (ref "U11") (pin "2") (pinfunction "Bypass_2") (pintype "input"))
    )
    (net (code "112") (name "Net-(U11-INN)") (class "Default")
      (node (ref "R43") (pin "1") (pinfunction "1_1") (pintype "input"))
      (node (ref "U11") (pin "4") (pinfunction "INN_4") (pintype "input"))
    )
    (net (code "113") (name "Net-(U11-INP)") (class "Default")
      (node (ref "R42") (pin "1") (pinfunction "1_1") (pintype "input"))
      (node (ref "U11") (pin "3") (pinfunction "INP_3") (pintype "input"))
    )
    (net (code "114") (name "Net-(U11-VCC)") (class "Default")
      (node (ref "C74") (pin "2") (pinfunction "2_2") (pintype "input"))
      (node (ref "C75") (pin "1") (pinfunction "1_1") (pintype "unspecified"))
      (node (ref "C76") (pin "1") (pinfunction "1_1") (pintype "unspecified"))
      (node (ref "R44") (pin "1") (pinfunction "1_1") (pintype "input"))
      (node (ref "U11") (pin "6") (pinfunction "VCC_6") (pintype "input"))
    )
    (net (code "115") (name "Net-(U11-VON)") (class "Default")
      (node (ref "R41") (pin "1") (pinfunction "1_1") (pintype "input"))
      (node (ref "U11") (pin "5") (pinfunction "VON_5") (pintype "input"))
    )
    (net (code "116") (name "Net-(U11-VoP)") (class "Default")
      (node (ref "R39") (pin "1") (pinfunction "1_1") (pintype "input"))
      (node (ref "U11") (pin "8") (pinfunction "VoP_8") (pintype "input"))
    )
    (net (code "117") (name "Net-(USB1-CC1)") (class "Default")
      (node (ref "R11") (pin "2") (pinfunction "2_2") (pintype "input"))
      (node (ref "USB1") (pin "A5") (pinfunction "CC1_A5") (pintype "unspecified"))
    )
    (net (code "118") (name "Net-(USB1-CC2)") (class "Default")
      (node (ref "R12") (pin "1") (pinfunction "1_1") (pintype "input"))
      (node (ref "USB1") (pin "B5") (pinfunction "CC2_B5") (pintype "unspecified"))
    )
    (net (code "119") (name "OUTN") (class "Default")
      (node (ref "C73") (pin "1") (pinfunction "1_1") (pintype "input"))
      (node (ref "C78") (pin "2") (pinfunction "2_2") (pintype "input"))
      (node (ref "R29") (pin "2") (pinfunction "2_2") (pintype "input"))
      (node (ref "R35") (pin "1") (pinfunction "1_1") (pintype "input"))
    )
    (net (code "120") (name "OUTP") (class "Default")
      (node (ref "C72") (pin "1") (pinfunction "1_1") (pintype "input"))
      (node (ref "C77") (pin "2") (pinfunction "2_2") (pintype "input"))
      (node (ref "R31") (pin "2") (pinfunction "2_2") (pintype "input"))
      (node (ref "R34") (pin "1") (pinfunction "1_1") (pintype "input"))
    )
    (net (code "121") (name "PA_EN") (class "Default")
      (node (ref "R40") (pin "1") (pinfunction "1_1") (pintype "input"))
      (node (ref "U11") (pin "1") (pinfunction "CTRL_1") (pintype "input"))
      (node (ref "U2") (pin "7") (pinfunction "IO1_7") (pintype "bidirectional"))
    )
    (net (code "122") (name "RESET") (class "Default")
      (node (ref "C7") (pin "1") (pinfunction "1_1") (pintype "input"))
      (node (ref "J4") (pin "4") (pinfunction "RST_4") (pintype "input"))
      (node (ref "J5") (pin "5") (pinfunction "RESET_5") (pintype "input"))
      (node (ref "J6") (pin "6") (pinfunction "6_6") (pintype "unspecified"))
      (node (ref "Q1") (pin "6") (pinfunction "C_6") (pintype "unspecified"))
      (node (ref "R1") (pin "2") (pinfunction "2_2") (pintype "input"))
      (node (ref "SW1") (pin "2") (pinfunction "2_2") (pintype "unspecified"))
      (node (ref "U1") (pin "3") (pinfunction "EN_3") (pintype "unspecified"))
      (node (ref "U2") (pin "15") (pinfunction "RESET#_15") (pintype "unspecified"))
    )
    (net (code "123") (name "RTS") (class "Default")
      (node (ref "Q1") (pin "1") (pinfunction "E_1") (pintype "unspecified"))
      (node (ref "R14") (pin "2") (pinfunction "2_2") (pintype "input"))
      (node (ref "U4") (pin "6") (pinfunction "RTS#_6") (pintype "unspecified"))
    )
    (net (code "124") (name "U0RXD") (class "Default")
      (node (ref "U1") (pin "36") (pinfunction "RXD0_36") (pintype "unspecified"))
      (node (ref "U4") (pin "8") (pinfunction "TXD_8") (pintype "unspecified"))
    )
    (net (code "125") (name "U0TXD") (class "Default")
      (node (ref "U1") (pin "37") (pinfunction "TXD0_37") (pintype "unspecified"))
      (node (ref "U4") (pin "9") (pinfunction "RXD_9") (pintype "unspecified"))
    )
    (net (code "126") (name "USB_D+") (class "Default")
      (node (ref "D11") (pin "2") (pinfunction "2_2") (pintype "input"))
      (node (ref "U5") (pin "15") (pinfunction "DPU_15") (pintype "unspecified"))
      (node (ref "USB1") (pin "A6") (pinfunction "D+_A6") (pintype "unspecified"))
      (node (ref "USB1") (pin "B6") (pinfunction "D+_B6") (pintype "unspecified"))
    )
    (net (code "127") (name "USB_D-") (class "Default")
      (node (ref "D13") (pin "2") (pinfunction "2_2") (pintype "input"))
      (node (ref "U5") (pin "14") (pinfunction "DMU_14") (pintype "unspecified"))
      (node (ref "USB1") (pin "A7") (pinfunction "D-_A7") (pintype "unspecified"))
      (node (ref "USB1") (pin "B7") (pinfunction "D-_B7") (pintype "unspecified"))
    )
    (net (code "128") (name "VBUS") (class "Default")
      (node (ref "C1") (pin "3") (pinfunction "OUT_3") (pintype "input"))
      (node (ref "C2") (pin "3") (pinfunction "OUT_3") (pintype "input"))
      (node (ref "C23") (pin "1") (pinfunction "1_1") (pintype "input"))
      (node (ref "C24") (pin "2") (pinfunction "2_2") (pintype "unspecified"))
      (node (ref "C31") (pin "1") (pinfunction "1_1") (pintype "input"))
      (node (ref "C32") (pin "2") (pinfunction "2_2") (pintype "unspecified"))
      (node (ref "F1") (pin "1") (pinfunction "1_1") (pintype "unspecified"))
      (node (ref "R15") (pin "2") (pinfunction "2_2") (pintype "input"))
      (node (ref "R19") (pin "2") (pinfunction "2_2") (pintype "input"))
      (node (ref "R44") (pin "2") (pinfunction "2_2") (pintype "input"))
      (node (ref "U6") (pin "4") (pinfunction "IN_4") (pintype "input"))
      (node (ref "U8") (pin "4") (pinfunction "IN_4") (pintype "input"))
    )
    (net (code "129") (name "unconnected-(J3-PadCD)") (class "Default")
      (node (ref "J3") (pin "CD") (pinfunction "CD_CD") (pintype "unspecified+no_connect"))
    )
    (net (code "130") (name "unconnected-(J5-EINT-Pad2)") (class "Default")
      (node (ref "J5") (pin "2") (pinfunction "EINT_2") (pintype "input+no_connect"))
    )
    (net (code "131") (name "unconnected-(J6-Pad1)") (class "Default")
      (node (ref "J6") (pin "1") (pinfunction "1_1") (pintype "unspecified+no_connect"))
    )
    (net (code "132") (name "unconnected-(J6-Pad4)") (class "Default")
      (node (ref "J6") (pin "4") (pinfunction "4_4") (pintype "unspecified+no_connect"))
    )
    (net (code "133") (name "unconnected-(J6-Pad10)") (class "Default")
      (node (ref "J6") (pin "10") (pinfunction "10_10") (pintype "unspecified+no_connect"))
    )
    (net (code "134") (name "unconnected-(J6-Pad23)") (class "Default")
      (node (ref "J6") (pin "23") (pinfunction "23_23") (pintype "unspecified+no_connect"))
    )
    (net (code "135") (name "unconnected-(J6-Pad24)") (class "Default")
      (node (ref "J6") (pin "24") (pinfunction "24_24") (pintype "unspecified+no_connect"))
    )
    (net (code "136") (name "unconnected-(U1-IO35-Pad28)") (class "Default")
      (node (ref "U1") (pin "28") (pinfunction "IO35_28") (pintype "unspecified+no_connect"))
    )
    (net (code "137") (name "unconnected-(U1-IO36-Pad29)") (class "Default")
      (node (ref "U1") (pin "29") (pinfunction "IO36_29") (pintype "unspecified+no_connect"))
    )
    (net (code "138") (name "unconnected-(U1-IO37-Pad30)") (class "Default")
      (node (ref "U1") (pin "30") (pinfunction "IO37_30") (pintype "unspecified+no_connect"))
    )
    (net (code "139") (name "unconnected-(U2-IO3-Pad10)") (class "Default")
      (node (ref "U2") (pin "10") (pinfunction "IO3_10") (pintype "bidirectional+no_connect"))
    )
    (net (code "140") (name "unconnected-(U2-IO4-Pad11)") (class "Default")
      (node (ref "U2") (pin "11") (pinfunction "IO4_11") (pintype "bidirectional+no_connect"))
    )
    (net (code "141") (name "unconnected-(U2-IO5-Pad12)") (class "Default")
      (node (ref "U2") (pin "12") (pinfunction "IO5_12") (pintype "bidirectional+no_connect"))
    )
    (net (code "142") (name "unconnected-(U2-IO6-Pad13)") (class "Default")
      (node (ref "U2") (pin "13") (pinfunction "IO6_13") (pintype "bidirectional+no_connect"))
    )
    (net (code "143") (name "unconnected-(U2-IO7-Pad14)") (class "Default")
      (node (ref "U2") (pin "14") (pinfunction "IO7_14") (pintype "bidirectional+no_connect"))
    )
    (net (code "144") (name "unconnected-(U3-CS-AUX-Pad10)") (class "Default")
      (node (ref "U3") (pin "10") (pinfunction "CS-AUX_10") (pintype "unspecified+no_connect"))
    )
    (net (code "145") (name "unconnected-(U3-INT1-Pad4)") (class "Default")
      (node (ref "U3") (pin "4") (pinfunction "INT1_4") (pintype "unspecified+no_connect"))
    )
    (net (code "146") (name "unconnected-(U3-INT2-Pad9)") (class "Default")
      (node (ref "U3") (pin "9") (pinfunction "INT2_9") (pintype "unspecified+no_connect"))
    )
    (net (code "147") (name "unconnected-(U3-SDO-AUX-Pad11)") (class "Default")
      (node (ref "U3") (pin "11") (pinfunction "SDO-AUX_11") (pintype "unspecified+no_connect"))
    )
    (net (code "148") (name "unconnected-(U3-SDO{slash}SA0-Pad1)") (class "Default")
      (node (ref "U3") (pin "1") (pinfunction "SDO/SA0_1") (pintype "unspecified+no_connect"))
    )
    (net (code "149") (name "unconnected-(U4-CTS#-Pad5)") (class "Default")
      (node (ref "U4") (pin "5") (pinfunction "CTS#_5") (pintype "unspecified+no_connect"))
    )
    (net (code "150") (name "unconnected-(U5-DM1-Pad11)") (class "Default")
      (node (ref "U5") (pin "11") (pinfunction "DM1_11") (pintype "unspecified+no_connect"))
    )
    (net (code "151") (name "unconnected-(U5-DM2-Pad9)") (class "Default")
      (node (ref "U5") (pin "9") (pinfunction "DM2_9") (pintype "unspecified+no_connect"))
    )
    (net (code "152") (name "unconnected-(U5-DP1-Pad12)") (class "Default")
      (node (ref "U5") (pin "12") (pinfunction "DP1_12") (pintype "unspecified+no_connect"))
    )
    (net (code "153") (name "unconnected-(U5-DP2-Pad10)") (class "Default")
      (node (ref "U5") (pin "10") (pinfunction "DP2_10") (pintype "unspecified+no_connect"))
    )
    (net (code "154") (name "unconnected-(U5-LED1-Pad22)") (class "Default")
      (node (ref "U5") (pin "22") (pinfunction "LED1_22") (pintype "unspecified+no_connect"))
    )
    (net (code "155") (name "unconnected-(U5-LED2-Pad23)") (class "Default")
      (node (ref "U5") (pin "23") (pinfunction "LED2_23") (pintype "unspecified+no_connect"))
    )
    (net (code "156") (name "unconnected-(U5-LED3{slash}SCL-Pad13)") (class "Default")
      (node (ref "U5") (pin "13") (pinfunction "LED3/SCL_13") (pintype "unspecified+no_connect"))
    )
    (net (code "157") (name "unconnected-(U5-LED4{slash}SDA-Pad21)") (class "Default")
      (node (ref "U5") (pin "21") (pinfunction "LED4/SDA_21") (pintype "unspecified+no_connect"))
    )
    (net (code "158") (name "unconnected-(U5-NC-Pad17)") (class "Default")
      (node (ref "U5") (pin "17") (pinfunction "NC_17") (pintype "unspecified+no_connect"))
    )
    (net (code "159") (name "unconnected-(U5-NC.-Pad2)") (class "Default")
      (node (ref "U5") (pin "2") (pinfunction "NC._2") (pintype "unspecified+no_connect"))
    )
    (net (code "160") (name "unconnected-(U5-OVCUR-Pad1)") (class "Default")
      (node (ref "U5") (pin "1") (pinfunction "OVCUR_1") (pintype "unspecified+no_connect"))
    )
    (net (code "161") (name "unconnected-(U5-PSELF-Pad18)") (class "Default")
      (node (ref "U5") (pin "18") (pinfunction "PSELF_18") (pintype "unspecified+no_connect"))
    )
    (net (code "162") (name "unconnected-(U5-PWREN-Pad24)") (class "Default")
      (node (ref "U5") (pin "24") (pinfunction "PWREN_24") (pintype "unspecified+no_connect"))
    )
    (net (code "163") (name "unconnected-(U5-RESET{slash}CDP-Pad16)") (class "Default")
      (node (ref "U5") (pin "16") (pinfunction "RESET/CDP_16") (pintype "unspecified+no_connect"))
    )
    (net (code "164") (name "unconnected-(U7-NC-Pad4)") (class "Default")
      (node (ref "U7") (pin "4") (pinfunction "NC_4") (pintype "unspecified+no_connect"))
    )
    (net (code "165") (name "unconnected-(U9-ASDOUT-Pad7)") (class "Default")
      (node (ref "U9") (pin "7") (pinfunction "ASDOUT_7") (pintype "input+no_connect"))
    )
    (net (code "166") (name "unconnected-(U9-MIC1N-Pad17)") (class "Default")
      (node (ref "U9") (pin "17") (pinfunction "MIC1N_17") (pintype "input+no_connect"))
    )
    (net (code "167") (name "unconnected-(U9-MIC1P{slash}DMIC_SDA-Pad18)") (class "Default")
      (node (ref "U9") (pin "18") (pinfunction "MIC1P/DMIC_SDA_18") (pintype "input+no_connect"))
    )
    (net (code "168") (name "unconnected-(U10-DMIC_CLK-Pad14)") (class "Default")
      (node (ref "U10") (pin "14") (pinfunction "DMIC_CLK_14") (pintype "input+no_connect"))
    )
    (net (code "169") (name "unconnected-(U10-INT-Pad13)") (class "Default")
      (node (ref "U10") (pin "13") (pinfunction "INT_13") (pintype "input+no_connect"))
    )
    (net (code "170") (name "unconnected-(USB1-SBU1-PadA8)") (class "Default")
      (node (ref "USB1") (pin "A8") (pinfunction "SBU1_A8") (pintype "unspecified+no_connect"))
    )
    (net (code "171") (name "unconnected-(USB1-SBU2-PadB8)") (class "Default")
      (node (ref "USB1") (pin "B8") (pinfunction "SBU2_B8") (pintype "unspecified+no_connect"))
    )
  )
)
